# zx80_SD_12_smd_build006_2_STM32.net
KiCad netlist of a schematic drawn in EAGLE
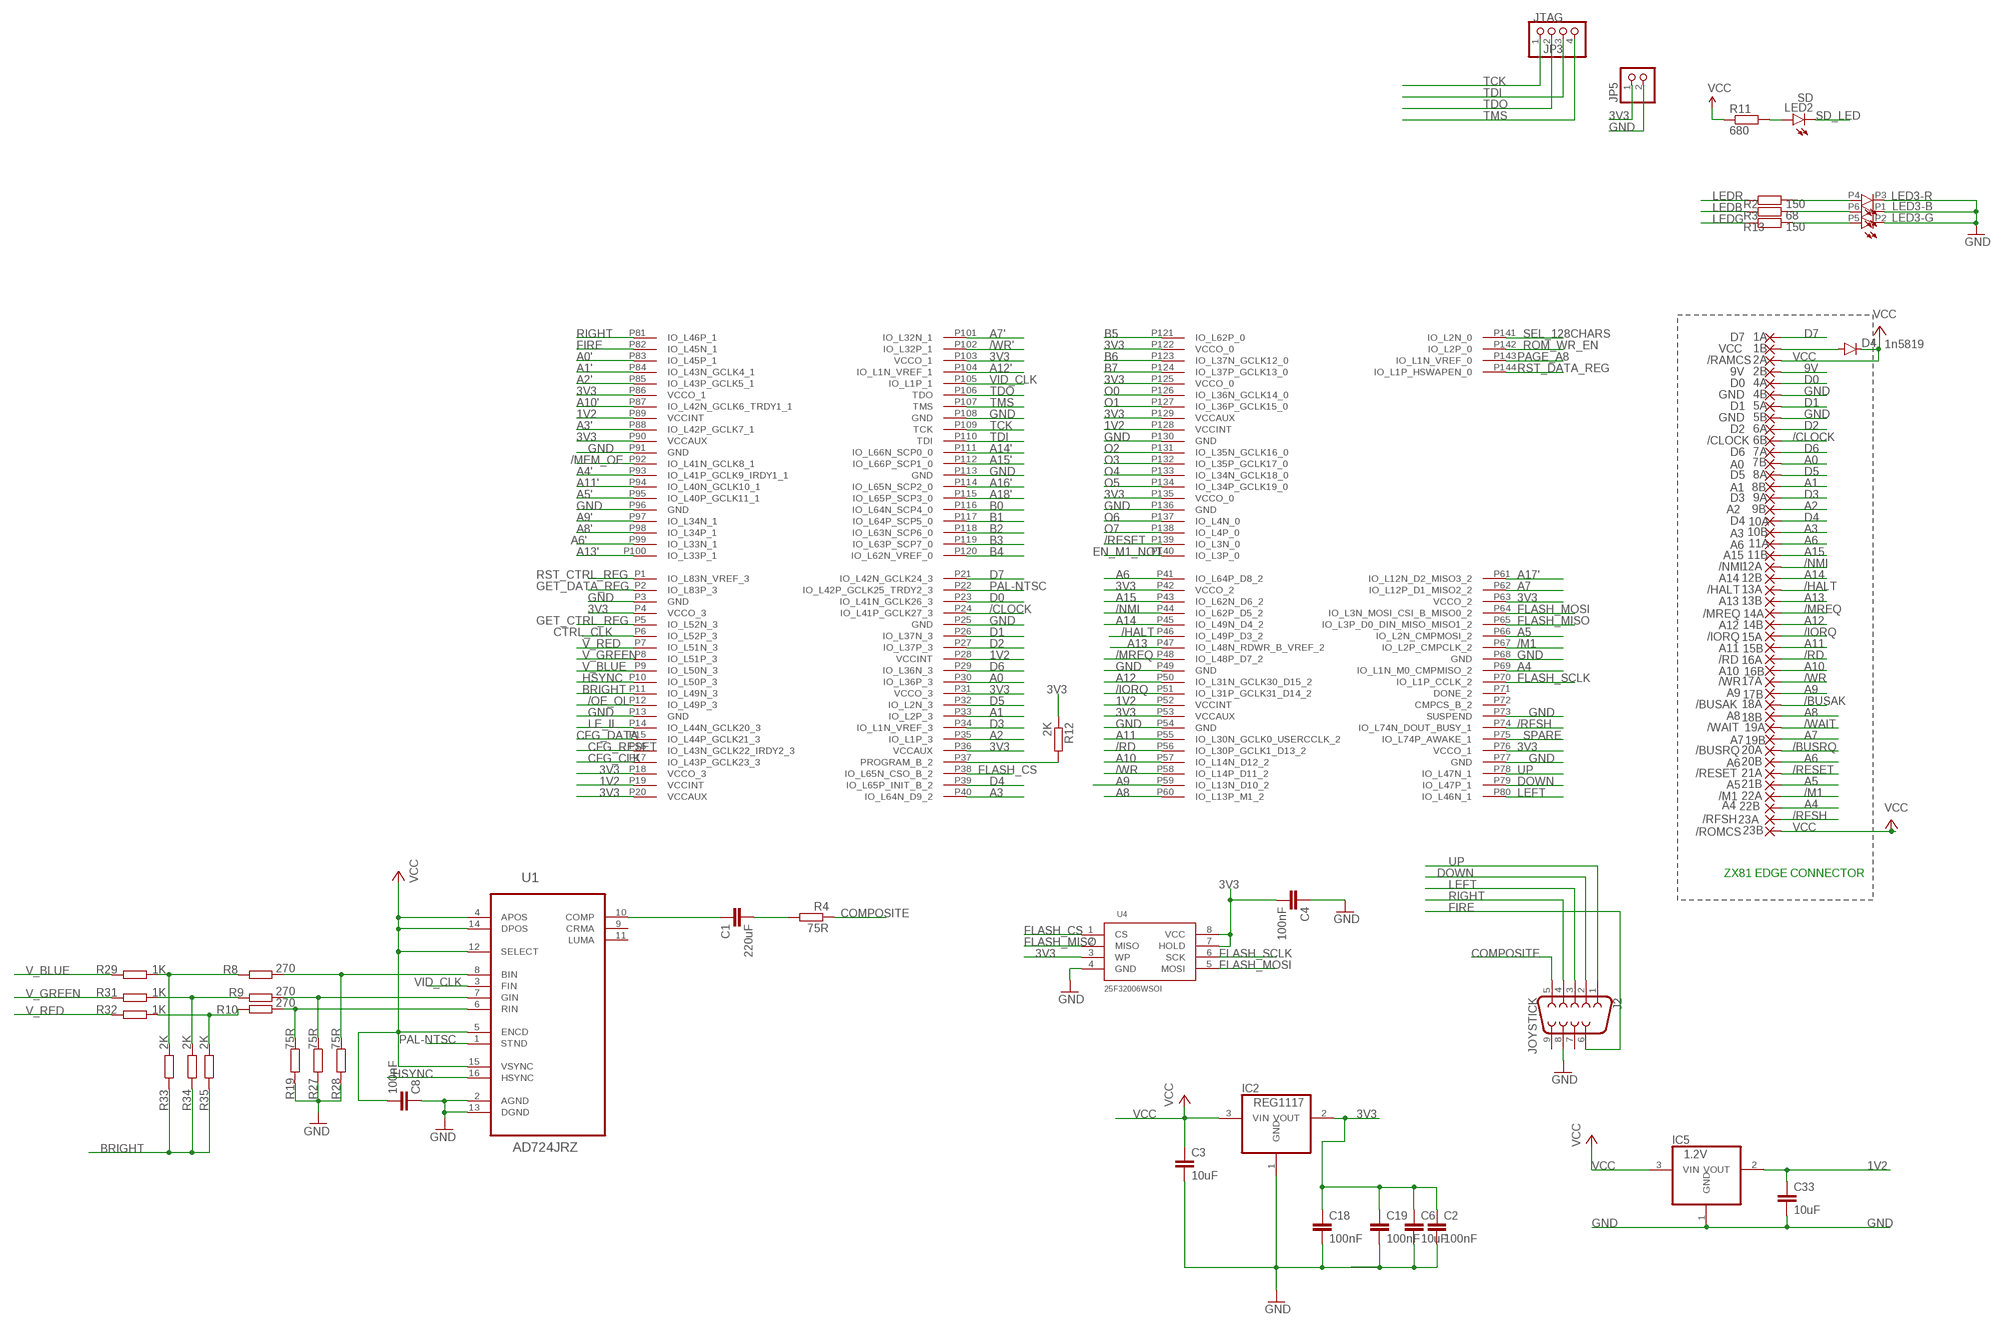
[diagram p0: schematic, sheet 1, part 1 of 2]
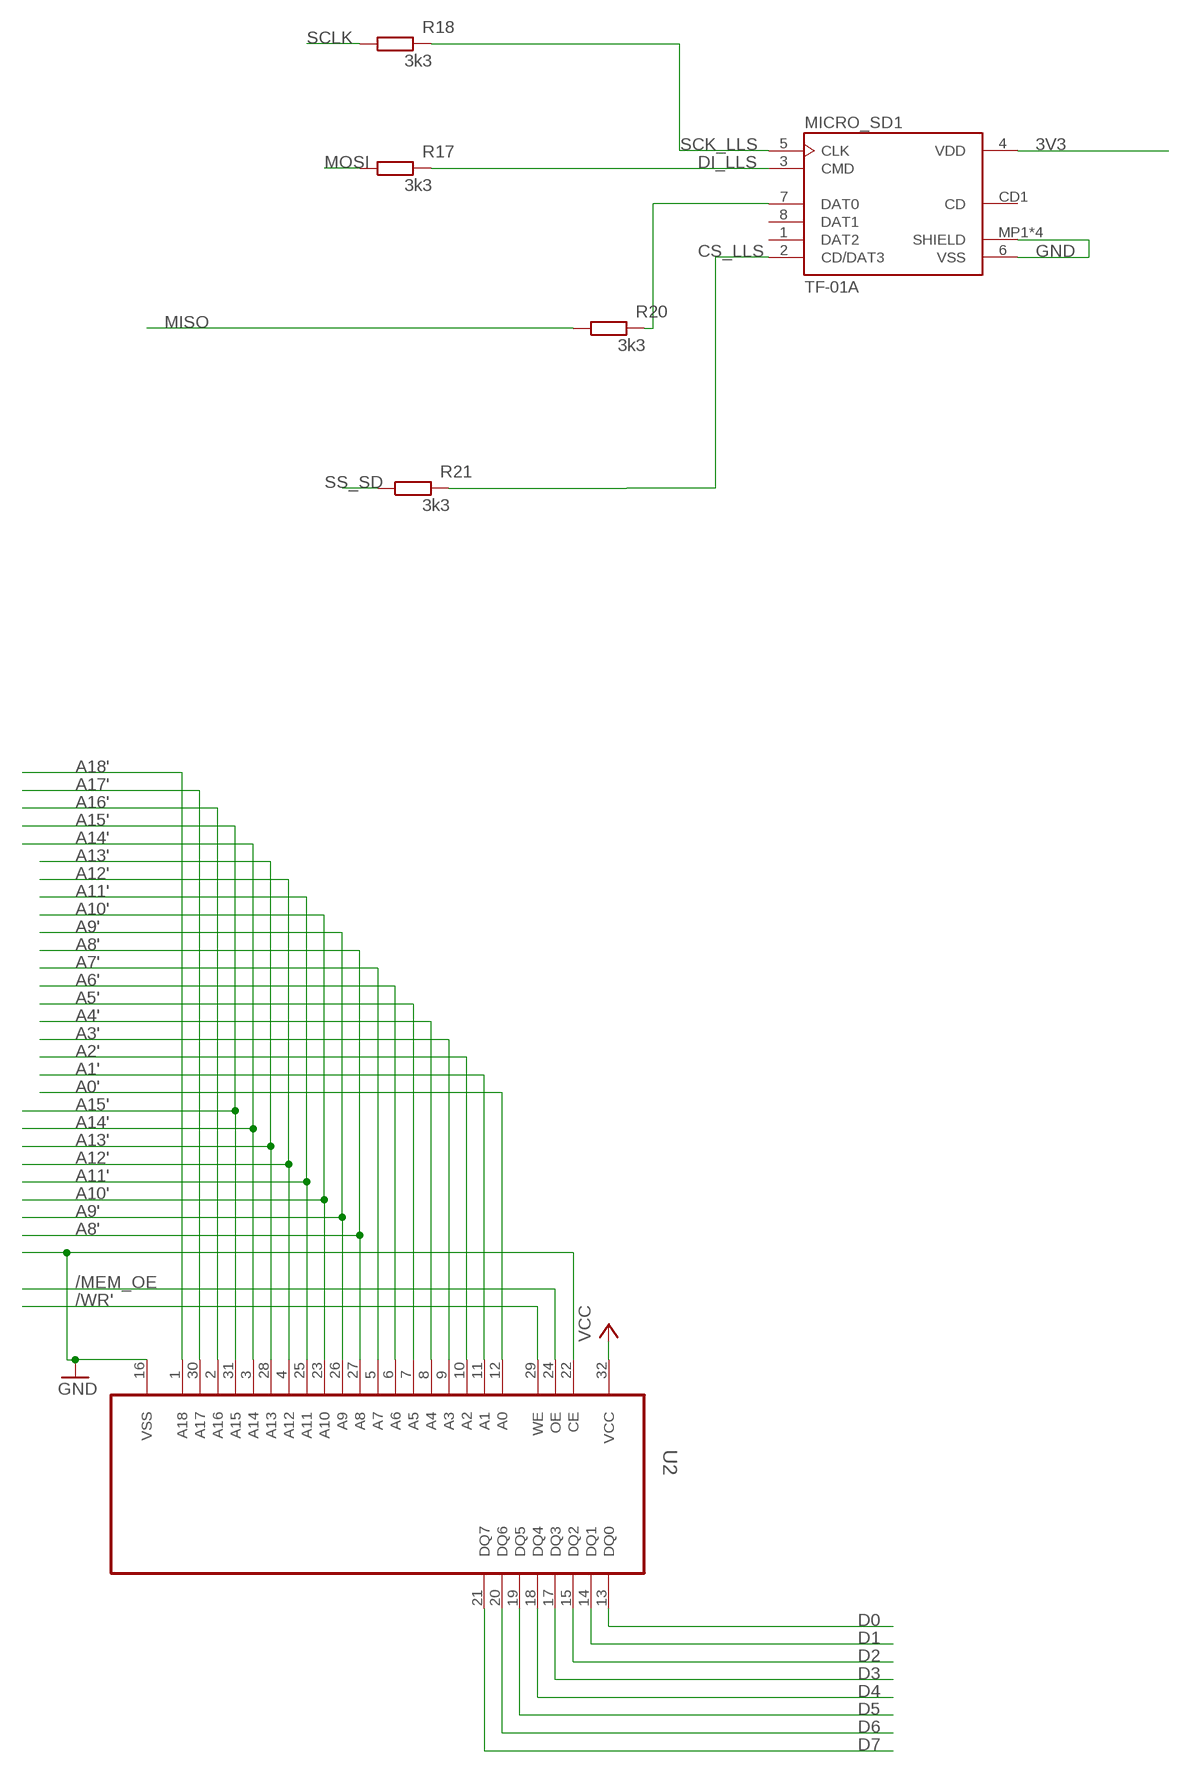
[diagram p1: schematic, sheet 1, part 2 of 2]
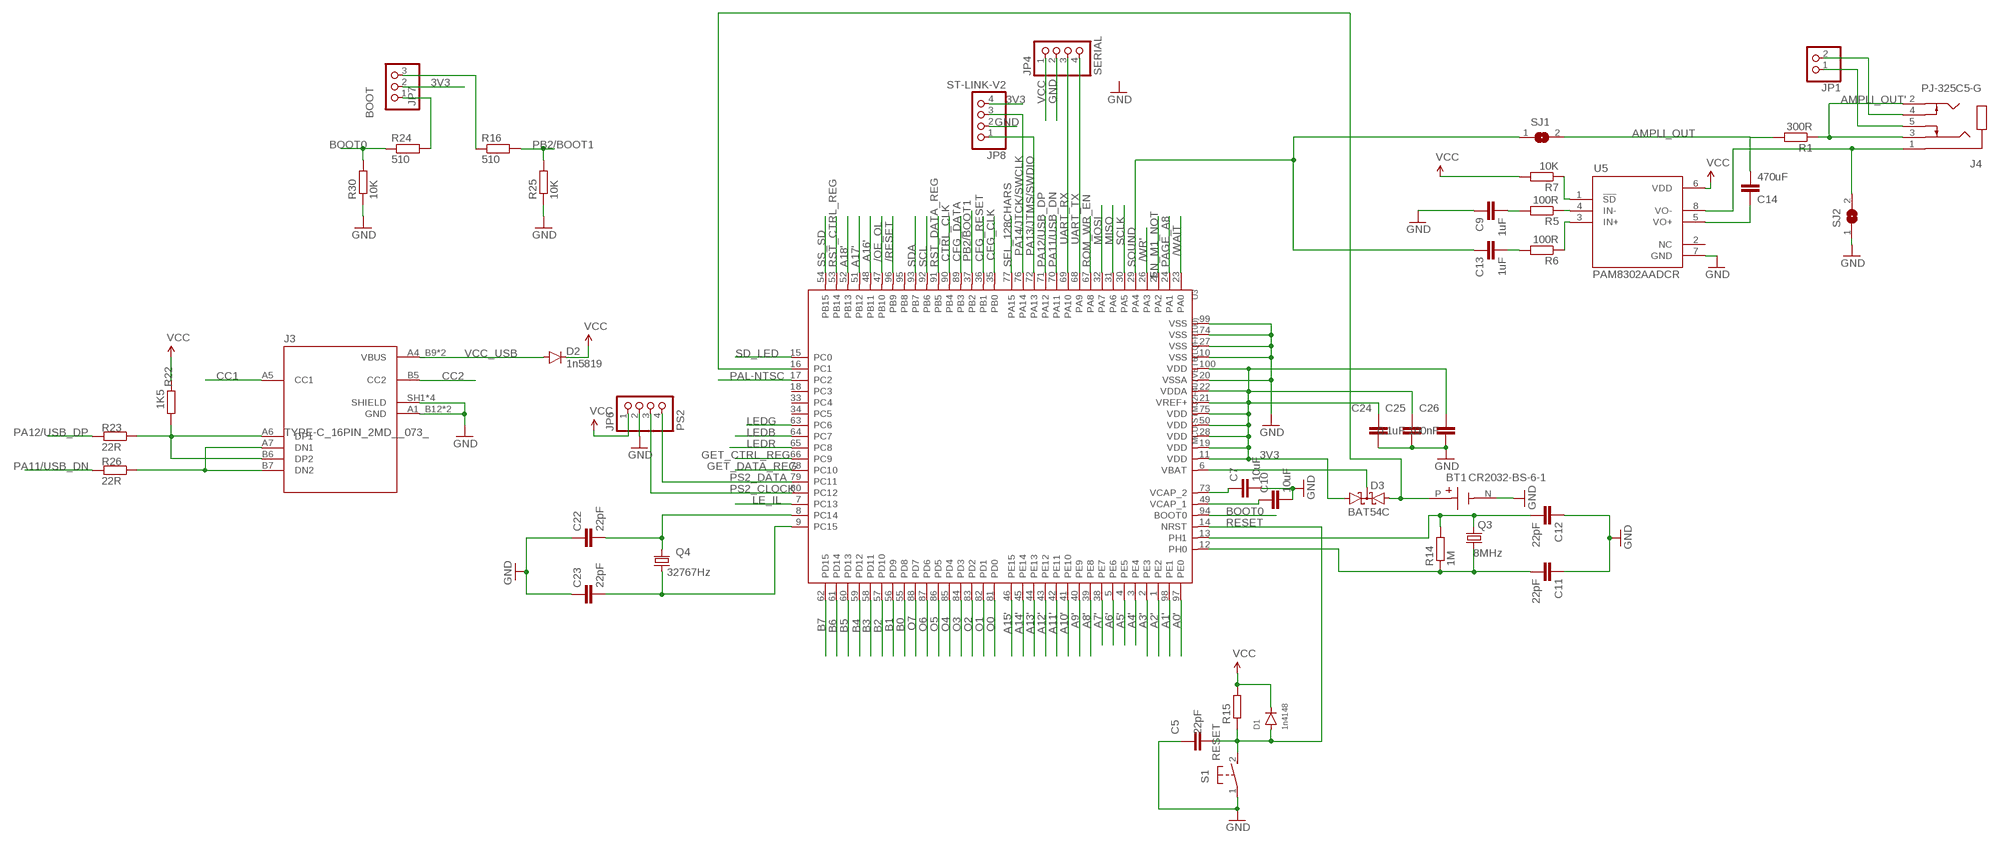
[diagram p2: schematic, sheet 2]

(export (version "E")
  (design (tool "Eeschema 10.0.6"))
  (components
    (comp (ref "BT1")
      (value "CR2032-BS-6-1")
      (footprint "eagle-import:BAT_CR2032-BS-6-1")
      (fields (field (name "MF") "Shenzhen Q&J Electronics Co. Ltd"))
      (libsource (lib "eagle-import") (part "CR2032-BS-6-1"))
    )
    (comp (ref "C5")
      (value "22pF")
      (footprint "eagle-import:C0603")
      (libsource (lib "eagle-import") (part "C-EUC0603"))
    )
    (comp (ref "C7")
      (value "10uF")
      (footprint "eagle-import:C1206")
      (libsource (lib "eagle-import") (part "C-EUC1206"))
    )
    (comp (ref "C9")
      (value "1uF")
      (footprint "eagle-import:C0603")
      (libsource (lib "eagle-import") (part "C-EUC0603"))
    )
    (comp (ref "C10")
      (value "10uF")
      (footprint "eagle-import:C1206")
      (libsource (lib "eagle-import") (part "C-EUC1206"))
    )
    (comp (ref "C11")
      (value "22pF")
      (footprint "eagle-import:C0603")
      (libsource (lib "eagle-import") (part "C-EUC0603"))
    )
    (comp (ref "C12")
      (value "22pF")
      (footprint "eagle-import:C0603")
      (libsource (lib "eagle-import") (part "C-EUC0603"))
    )
    (comp (ref "C13")
      (value "1uF")
      (footprint "eagle-import:C0603")
      (libsource (lib "eagle-import") (part "C-EUC0603"))
    )
    (comp (ref "C14")
      (value "470uF")
      (footprint "eagle-import:C0603")
      (libsource (lib "eagle-import") (part "C-EUC0603"))
    )
    (comp (ref "C22")
      (value "22pF")
      (footprint "eagle-import:C0603")
      (libsource (lib "eagle-import") (part "C-EUC0603"))
    )
    (comp (ref "C23")
      (value "22pF")
      (footprint "eagle-import:C0603")
      (libsource (lib "eagle-import") (part "C-EUC0603"))
    )
    (comp (ref "C24")
      (value "0.1uF")
      (footprint "eagle-import:C0603")
      (libsource (lib "eagle-import") (part "C-EUC0603"))
    )
    (comp (ref "C25")
      (value "0.1uF")
      (footprint "eagle-import:C0603")
      (libsource (lib "eagle-import") (part "C-EUC0603"))
    )
    (comp (ref "C26")
      (value "100nF")
      (footprint "eagle-import:C0603")
      (libsource (lib "eagle-import") (part "C-EUC0603"))
    )
    (comp (ref "D1")
      (value "1n4148")
      (footprint "eagle-import:SOD123")
      (libsource (lib "eagle-import") (part "DIODE-SOD123"))
    )
    (comp (ref "D2")
      (value "1n5819")
      (footprint "eagle-import:SOD323-W")
      (libsource (lib "eagle-import") (part "DIODE-SOD323-W"))
    )
    (comp (ref "D3")
      (value "BAT54C")
      (footprint "eagle-import:SOT23")
      (libsource (lib "eagle-import") (part "BAT54C"))
    )
    (comp (ref "J3")
      (value "TYPE-C_16PIN_2MD__073_")
      (footprint "eagle-import:SHOUHAN_TYPE-C_16PIN_2MD__073_")
      (fields (field (name "MF") "Shouhan") (field (name "MP") "TYPE-C 16PIN 2MD (073)"))
      (libsource (lib "eagle-import") (part "TYPE-C_16PIN_2MD__073_"))
    )
    (comp (ref "J4")
      (value "PJ-325C5-G")
      (footprint "eagle-import:XKB_PJ-325C5-G")
      (fields (field (name "MF") "XKB Connection"))
      (libsource (lib "eagle-import") (part "PJ-325C5-G"))
    )
    (comp (ref "JP1")
      (value "PINHD-1X2")
      (footprint "eagle-import:1X02")
      (libsource (lib "eagle-import") (part "PINHD-1X2"))
    )
    (comp (ref "JP4")
      (value "SERIAL")
      (footprint "eagle-import:1X04")
      (libsource (lib "eagle-import") (part "PINHD-1X4"))
    )
    (comp (ref "JP6")
      (value "PS2")
      (footprint "eagle-import:1X04")
      (libsource (lib "eagle-import") (part "PINHD-1X4"))
    )
    (comp (ref "JP7")
      (value "BOOT")
      (footprint "eagle-import:1X03")
      (libsource (lib "eagle-import") (part "PINHD-1X3"))
    )
    (comp (ref "JP8")
      (value "ST-LINK-V2")
      (footprint "eagle-import:1X04")
      (libsource (lib "eagle-import") (part "PINHD-1X4"))
    )
    (comp (ref "Q3")
      (value "8MHz")
      (footprint "eagle-import:3.2X2.5_KX-7")
      (libsource (lib "eagle-import") (part "KX-7"))
    )
    (comp (ref "Q4")
      (value "32767Hz")
      (footprint "eagle-import:3.2X1.5")
      (libsource (lib "eagle-import") (part "KX-327-NHT"))
    )
    (comp (ref "R1")
      (value "300R")
      (footprint "eagle-import:R0603")
      (libsource (lib "eagle-import") (part "R-EU_R0603"))
    )
    (comp (ref "R5")
      (value "100R")
      (footprint "eagle-import:R0603")
      (libsource (lib "eagle-import") (part "R-EU_R0603"))
    )
    (comp (ref "R6")
      (value "100R")
      (footprint "eagle-import:R0603")
      (libsource (lib "eagle-import") (part "R-EU_R0603"))
    )
    (comp (ref "R7")
      (value "10K")
      (footprint "eagle-import:R0603")
      (libsource (lib "eagle-import") (part "R-EU_R0603"))
    )
    (comp (ref "R14")
      (value "1M")
      (footprint "eagle-import:R0603")
      (libsource (lib "eagle-import") (part "R-EU_R0603"))
    )
    (comp (ref "R15")
      (value "3K3")
      (footprint "eagle-import:R0603")
      (libsource (lib "eagle-import") (part "R-EU_R0603"))
    )
    (comp (ref "R16")
      (value "510")
      (footprint "eagle-import:R0603")
      (libsource (lib "eagle-import") (part "R-EU_R0603"))
    )
    (comp (ref "R22")
      (value "1K5")
      (footprint "eagle-import:R0603")
      (libsource (lib "eagle-import") (part "R-EU_R0603"))
    )
    (comp (ref "R23")
      (value "22R")
      (footprint "eagle-import:R0603")
      (libsource (lib "eagle-import") (part "R-EU_R0603"))
    )
    (comp (ref "R24")
      (value "510")
      (footprint "eagle-import:R0603")
      (libsource (lib "eagle-import") (part "R-EU_R0603"))
    )
    (comp (ref "R25")
      (value "10K")
      (footprint "eagle-import:R0603")
      (libsource (lib "eagle-import") (part "R-EU_R0603"))
    )
    (comp (ref "R26")
      (value "22R")
      (footprint "eagle-import:R0603")
      (libsource (lib "eagle-import") (part "R-EU_R0603"))
    )
    (comp (ref "R30")
      (value "10K")
      (footprint "eagle-import:R0603")
      (libsource (lib "eagle-import") (part "R-EU_R0603"))
    )
    (comp (ref "S1")
      (value "RESET")
      (footprint "eagle-import:B3F-31XX")
      (fields (field (name "MPN") "B3F-3100"))
      (libsource (lib "eagle-import") (part "31-XX"))
    )
    (comp (ref "SJ1") (value "SJ") (footprint "eagle-import:SJ") (libsource (lib "eagle-import") (part "SJ")))
    (comp (ref "SJ2") (value "SJ") (footprint "eagle-import:SJ") (libsource (lib "eagle-import") (part "SJ")))
    (comp (ref "U3")
      (value "MCU-STM32F407VET6(LQFP100)")
      (footprint "eagle-import:LQFP100-0.5-13.8X13.8MM")
      (fields (field (name "MF") "STMicroelectronics") (field (name "MP") "STM32F407VET6"))
      (libsource (lib "eagle-import") (part "MCU-STM32F407VET6(LQFP100)"))
    )
    (comp (ref "U5")
      (value "PAM8302AADCR")
      (footprint "eagle-import:SOIC127P600X170-8N")
      (fields (field (name "MF") "Diodes Inc."))
      (libsource (lib "eagle-import") (part "PAM8302AADCR"))
    )
    (comp (ref "1A")
      (value "D7")
      (footprint "eagle-import:EDGEPIN")
      (libsource (lib "eagle-import") (part "SMD2EDGEPIN"))
    )
    (comp (ref "1B")
      (value "VCC")
      (footprint "eagle-import:EDGEPIN")
      (libsource (lib "eagle-import") (part "SMD2EDGEPIN"))
    )
    (comp (ref "2A")
      (value "/RAMCS")
      (footprint "eagle-import:EDGEPIN")
      (libsource (lib "eagle-import") (part "SMD2EDGEPIN"))
    )
    (comp (ref "2B")
      (value "9V")
      (footprint "eagle-import:EDGEPIN")
      (libsource (lib "eagle-import") (part "SMD2EDGEPIN"))
    )
    (comp (ref "4A")
      (value "D0")
      (footprint "eagle-import:EDGEPIN")
      (libsource (lib "eagle-import") (part "SMD2EDGEPIN"))
    )
    (comp (ref "4B")
      (value "GND")
      (footprint "eagle-import:EDGEPIN")
      (libsource (lib "eagle-import") (part "SMD2EDGEPIN"))
    )
    (comp (ref "5A")
      (value "D1")
      (footprint "eagle-import:EDGEPIN")
      (libsource (lib "eagle-import") (part "SMD2EDGEPIN"))
    )
    (comp (ref "5B")
      (value "GND")
      (footprint "eagle-import:EDGEPIN")
      (libsource (lib "eagle-import") (part "SMD2EDGEPIN"))
    )
    (comp (ref "6A")
      (value "D2")
      (footprint "eagle-import:EDGEPIN")
      (libsource (lib "eagle-import") (part "SMD2EDGEPIN"))
    )
    (comp (ref "6B")
      (value "/CLOCK")
      (footprint "eagle-import:EDGEPIN")
      (libsource (lib "eagle-import") (part "SMD2EDGEPIN"))
    )
    (comp (ref "7A")
      (value "D6")
      (footprint "eagle-import:EDGEPIN")
      (libsource (lib "eagle-import") (part "SMD2EDGEPIN"))
    )
    (comp (ref "7B")
      (value "A0")
      (footprint "eagle-import:EDGEPIN")
      (libsource (lib "eagle-import") (part "SMD2EDGEPIN"))
    )
    (comp (ref "8A")
      (value "D5")
      (footprint "eagle-import:EDGEPIN")
      (libsource (lib "eagle-import") (part "SMD2EDGEPIN"))
    )
    (comp (ref "8B")
      (value "A1")
      (footprint "eagle-import:EDGEPIN")
      (libsource (lib "eagle-import") (part "SMD2EDGEPIN"))
    )
    (comp (ref "9A")
      (value "D3")
      (footprint "eagle-import:EDGEPIN")
      (libsource (lib "eagle-import") (part "SMD2EDGEPIN"))
    )
    (comp (ref "9B")
      (value "A2")
      (footprint "eagle-import:EDGEPIN")
      (libsource (lib "eagle-import") (part "SMD2EDGEPIN"))
    )
    (comp (ref "10A")
      (value "D4")
      (footprint "eagle-import:EDGEPIN")
      (libsource (lib "eagle-import") (part "SMD2EDGEPIN"))
    )
    (comp (ref "10B")
      (value "A3")
      (footprint "eagle-import:EDGEPIN")
      (libsource (lib "eagle-import") (part "SMD2EDGEPIN"))
    )
    (comp (ref "11A")
      (value "A6")
      (footprint "eagle-import:EDGEPIN")
      (libsource (lib "eagle-import") (part "SMD2EDGEPIN"))
    )
    (comp (ref "11B")
      (value "A15")
      (footprint "eagle-import:EDGEPIN")
      (libsource (lib "eagle-import") (part "SMD2EDGEPIN"))
    )
    (comp (ref "12A")
      (value "/NMI")
      (footprint "eagle-import:EDGEPIN")
      (libsource (lib "eagle-import") (part "SMD2EDGEPIN"))
    )
    (comp (ref "12B")
      (value "A14")
      (footprint "eagle-import:EDGEPIN")
      (libsource (lib "eagle-import") (part "SMD2EDGEPIN"))
    )
    (comp (ref "13A")
      (value "/HALT")
      (footprint "eagle-import:EDGEPIN")
      (libsource (lib "eagle-import") (part "SMD2EDGEPIN"))
    )
    (comp (ref "13B")
      (value "A13")
      (footprint "eagle-import:EDGEPIN")
      (libsource (lib "eagle-import") (part "SMD2EDGEPIN"))
    )
    (comp (ref "14A")
      (value "/MREQ")
      (footprint "eagle-import:EDGEPIN")
      (libsource (lib "eagle-import") (part "SMD2EDGEPIN"))
    )
    (comp (ref "14B")
      (value "A12")
      (footprint "eagle-import:EDGEPIN")
      (libsource (lib "eagle-import") (part "SMD2EDGEPIN"))
    )
    (comp (ref "15A")
      (value "/IORQ")
      (footprint "eagle-import:EDGEPIN")
      (libsource (lib "eagle-import") (part "SMD2EDGEPIN"))
    )
    (comp (ref "15B")
      (value "A11")
      (footprint "eagle-import:EDGEPIN")
      (libsource (lib "eagle-import") (part "SMD2EDGEPIN"))
    )
    (comp (ref "16A")
      (value "/RD")
      (footprint "eagle-import:EDGEPIN")
      (libsource (lib "eagle-import") (part "SMD2EDGEPIN"))
    )
    (comp (ref "16B")
      (value "A10")
      (footprint "eagle-import:EDGEPIN")
      (libsource (lib "eagle-import") (part "SMD2EDGEPIN"))
    )
    (comp (ref "17A")
      (value "/WR")
      (footprint "eagle-import:EDGEPIN")
      (libsource (lib "eagle-import") (part "SMD2EDGEPIN"))
    )
    (comp (ref "17B")
      (value "A9")
      (footprint "eagle-import:EDGEPIN")
      (libsource (lib "eagle-import") (part "SMD2EDGEPIN"))
    )
    (comp (ref "18A")
      (value "/BUSAK")
      (footprint "eagle-import:EDGEPIN")
      (libsource (lib "eagle-import") (part "SMD2EDGEPIN"))
    )
    (comp (ref "18B")
      (value "A8")
      (footprint "eagle-import:EDGEPIN")
      (libsource (lib "eagle-import") (part "SMD2EDGEPIN"))
    )
    (comp (ref "19A")
      (value "/WAIT")
      (footprint "eagle-import:EDGEPIN")
      (libsource (lib "eagle-import") (part "SMD2EDGEPIN"))
    )
    (comp (ref "19B")
      (value "A7")
      (footprint "eagle-import:EDGEPIN")
      (libsource (lib "eagle-import") (part "SMD2EDGEPIN"))
    )
    (comp (ref "20A")
      (value "/BUSRQ")
      (footprint "eagle-import:EDGEPIN")
      (libsource (lib "eagle-import") (part "SMD2EDGEPIN"))
    )
    (comp (ref "20B")
      (value "A6")
      (footprint "eagle-import:EDGEPIN")
      (libsource (lib "eagle-import") (part "SMD2EDGEPIN"))
    )
    (comp (ref "21A")
      (value "/RESET")
      (footprint "eagle-import:EDGEPIN")
      (libsource (lib "eagle-import") (part "SMD2EDGEPIN"))
    )
    (comp (ref "21B")
      (value "A5")
      (footprint "eagle-import:EDGEPIN")
      (libsource (lib "eagle-import") (part "SMD2EDGEPIN"))
    )
    (comp (ref "22A")
      (value "/M1")
      (footprint "eagle-import:EDGEPIN")
      (libsource (lib "eagle-import") (part "SMD2EDGEPIN"))
    )
    (comp (ref "22B")
      (value "A4")
      (footprint "eagle-import:EDGEPIN")
      (libsource (lib "eagle-import") (part "SMD2EDGEPIN"))
    )
    (comp (ref "23A")
      (value "/RFSH")
      (footprint "eagle-import:EDGEPIN")
      (libsource (lib "eagle-import") (part "SMD2EDGEPIN"))
    )
    (comp (ref "23B")
      (value "/ROMCS")
      (footprint "eagle-import:EDGEPIN")
      (libsource (lib "eagle-import") (part "SMD2EDGEPIN"))
    )
    (comp (ref "C1")
      (value "220uF")
      (footprint "eagle-import:C0603K")
      (libsource (lib "eagle-import") (part "C-EUC0603K"))
    )
    (comp (ref "C2")
      (value "100nF")
      (footprint "eagle-import:C0603")
      (libsource (lib "eagle-import") (part "C-EUC0603"))
    )
    (comp (ref "C3")
      (value "10uF")
      (footprint "eagle-import:C0603")
      (libsource (lib "eagle-import") (part "C-EUC0603"))
    )
    (comp (ref "C4")
      (value "100nF")
      (footprint "eagle-import:C0603")
      (libsource (lib "eagle-import") (part "C-EUC0603"))
    )
    (comp (ref "C6")
      (value "10uF")
      (footprint "eagle-import:C0603")
      (libsource (lib "eagle-import") (part "C-EUC0603"))
    )
    (comp (ref "C8")
      (value "100nF")
      (footprint "eagle-import:C0603K")
      (libsource (lib "eagle-import") (part "C-EUC0603K"))
    )
    (comp (ref "C18")
      (value "100nF")
      (footprint "eagle-import:C0603")
      (libsource (lib "eagle-import") (part "C-EUC0603"))
    )
    (comp (ref "C19")
      (value "100nF")
      (footprint "eagle-import:C0603")
      (libsource (lib "eagle-import") (part "C-EUC0603"))
    )
    (comp (ref "C33")
      (value "10uF")
      (footprint "eagle-import:C0603")
      (libsource (lib "eagle-import") (part "C-EUC0603"))
    )
    (comp (ref "D4")
      (value "1n5819")
      (footprint "eagle-import:SOD323-W")
      (libsource (lib "eagle-import") (part "DIODE-SOD323-W"))
    )
    (comp (ref "IC2")
      (value "REG1117")
      (footprint "eagle-import:SOT223")
      (libsource (lib "eagle-import") (part "REG1117"))
    )
    (comp (ref "IC5")
      (value "1.2V")
      (footprint "eagle-import:SOT223")
      (fields (field (name "MPN") "REG1117"))
      (libsource (lib "eagle-import") (part "REG1117"))
    )
    (comp (ref "J2")
      (value "JOYSTICK")
      (footprint "eagle-import:DB9_MALE")
      (libsource (lib "eagle-import") (part "DB9MALE"))
    )
    (comp (ref "JP3")
      (value "JTAG")
      (footprint "eagle-import:1X04")
      (libsource (lib "eagle-import") (part "PINHD-1X4"))
    )
    (comp (ref "JP5")
      (value "PINHD-1X2")
      (footprint "eagle-import:1X02")
      (libsource (lib "eagle-import") (part "PINHD-1X2"))
    )
    (comp (ref "LED2")
      (value "SD")
      (footprint "eagle-import:CHIPLED_0805")
      (libsource (lib "eagle-import") (part "LEDCHIPLED_0805"))
    )
    (comp (ref "LED3")
      (value "STATUS")
      (footprint "eagle-import:3535-PLCC6")
      (libsource (lib "eagle-import") (part "3535RGB3535RGB"))
    )
    (comp (ref "MICRO_SD1")
      (value "TF-01A")
      (footprint "eagle-import:TF-01A")
      (fields (field (name "MF") "HRO Electronics Co., Ltd."))
      (libsource (lib "eagle-import") (part "TF-01A"))
    )
    (comp (ref "R2")
      (value "150")
      (footprint "eagle-import:R0603")
      (libsource (lib "eagle-import") (part "R-EU_R0603"))
    )
    (comp (ref "R3")
      (value "68")
      (footprint "eagle-import:R0603")
      (libsource (lib "eagle-import") (part "R-EU_R0603"))
    )
    (comp (ref "R4")
      (value "75R")
      (footprint "eagle-import:R0603")
      (libsource (lib "eagle-import") (part "R-EU_R0603"))
    )
    (comp (ref "R8")
      (value "270")
      (footprint "eagle-import:R0402")
      (libsource (lib "eagle-import") (part "R-EU_R0402"))
    )
    (comp (ref "R9")
      (value "270")
      (footprint "eagle-import:R0402")
      (libsource (lib "eagle-import") (part "R-EU_R0402"))
    )
    (comp (ref "R10")
      (value "270")
      (footprint "eagle-import:R0402")
      (libsource (lib "eagle-import") (part "R-EU_R0402"))
    )
    (comp (ref "R11")
      (value "680")
      (footprint "eagle-import:R0603")
      (libsource (lib "eagle-import") (part "R-EU_R0603"))
    )
    (comp (ref "R12")
      (value "2K")
      (footprint "eagle-import:R0603")
      (libsource (lib "eagle-import") (part "R-EU_R0603"))
    )
    (comp (ref "R13")
      (value "150")
      (footprint "eagle-import:R0603")
      (libsource (lib "eagle-import") (part "R-EU_R0603"))
    )
    (comp (ref "R17")
      (value "3k3")
      (footprint "eagle-import:R0603")
      (libsource (lib "eagle-import") (part "R-EU_R0603"))
    )
    (comp (ref "R18")
      (value "3k3")
      (footprint "eagle-import:R0603")
      (libsource (lib "eagle-import") (part "R-EU_R0603"))
    )
    (comp (ref "R19")
      (value "75R")
      (footprint "eagle-import:R0402")
      (libsource (lib "eagle-import") (part "R-EU_R0402"))
    )
    (comp (ref "R20")
      (value "3k3")
      (footprint "eagle-import:R0603")
      (libsource (lib "eagle-import") (part "R-EU_R0603"))
    )
    (comp (ref "R21")
      (value "3k3")
      (footprint "eagle-import:R0603")
      (libsource (lib "eagle-import") (part "R-EU_R0603"))
    )
    (comp (ref "R27")
      (value "75R")
      (footprint "eagle-import:R0402")
      (libsource (lib "eagle-import") (part "R-EU_R0402"))
    )
    (comp (ref "R28")
      (value "75R")
      (footprint "eagle-import:R0402")
      (libsource (lib "eagle-import") (part "R-EU_R0402"))
    )
    (comp (ref "R29")
      (value "1K")
      (footprint "eagle-import:R0402")
      (libsource (lib "eagle-import") (part "R-EU_R0402"))
    )
    (comp (ref "R31")
      (value "1K")
      (footprint "eagle-import:R0402")
      (libsource (lib "eagle-import") (part "R-EU_R0402"))
    )
    (comp (ref "R32")
      (value "1K")
      (footprint "eagle-import:R0402")
      (libsource (lib "eagle-import") (part "R-EU_R0402"))
    )
    (comp (ref "R33")
      (value "2K")
      (footprint "eagle-import:R0402")
      (libsource (lib "eagle-import") (part "R-EU_R0402"))
    )
    (comp (ref "R34")
      (value "2K")
      (footprint "eagle-import:R0402")
      (libsource (lib "eagle-import") (part "R-EU_R0402"))
    )
    (comp (ref "R35")
      (value "2K")
      (footprint "eagle-import:R0402")
      (libsource (lib "eagle-import") (part "R-EU_R0402"))
    )
    (comp (ref "U$1")
      (value "XC6SLX9-2TQG144C")
      (footprint "eagle-import:TQ144")
      (fields (field (name "MF") "Xilinx Inc."))
      (libsource (lib "eagle-import") (part "XC6SLX9-2TQG144C"))
    )
    (comp (ref "U1")
      (value "AD724JRZ")
      (footprint "eagle-import:SOIC127P1032X265-16N")
      (fields (field (name "MF") "Analog Devices") (field (name "MP") "AD724JR"))
      (libsource (lib "eagle-import") (part "AD724JRZ"))
    )
    (comp (ref "U2")
      (value "AS6C4008")
      (footprint "eagle-import:SOP32-5")
      (libsource (lib "eagle-import") (part "AS6C4008-55SINSOP5"))
    )
    (comp (ref "U4")
      (value "25F32006WSOI")
      (footprint "eagle-import:SO08-EIAJ")
      (libsource (lib "eagle-import") (part "SPI_FLASH-X25XXSMD1"))
    )
  )
  (nets
    (net (code "1") (name "1V2") (class "Default")
      (node (ref "C33") (pin "1") (pinfunction "1_1") (pintype "passive"))
      (node (ref "IC5") (pin "2") (pinfunction "VOUT_2") (pintype "output"))
      (node (ref "U$1") (pin "P128") (pinfunction "VCCINT_P128") (pintype "bidirectional"))
      (node (ref "U$1") (pin "P19") (pinfunction "VCCINT_P19") (pintype "bidirectional"))
      (node (ref "U$1") (pin "P28") (pinfunction "VCCINT_P28") (pintype "bidirectional"))
      (node (ref "U$1") (pin "P52") (pinfunction "VCCINT_P52") (pintype "bidirectional"))
      (node (ref "U$1") (pin "P89") (pinfunction "VCCINT_P89") (pintype "bidirectional"))
    )
    (net (code "2") (name "3V3") (class "Default")
      (node (ref "C18") (pin "1") (pinfunction "1_1") (pintype "passive"))
      (node (ref "C19") (pin "1") (pinfunction "1_1") (pintype "passive"))
      (node (ref "C2") (pin "1") (pinfunction "1_1") (pintype "passive"))
      (node (ref "C24") (pin "1") (pinfunction "1_1") (pintype "passive"))
      (node (ref "C25") (pin "1") (pinfunction "1_1") (pintype "passive"))
      (node (ref "C26") (pin "1") (pinfunction "1_1") (pintype "passive"))
      (node (ref "C4") (pin "2") (pinfunction "2_2") (pintype "passive"))
      (node (ref "C6") (pin "1") (pinfunction "1_1") (pintype "passive"))
      (node (ref "D3") (pin "1") (pinfunction "A1_1") (pintype "passive"))
      (node (ref "IC2") (pin "2") (pinfunction "VOUT_2") (pintype "output"))
      (node (ref "JP5") (pin "1") (pinfunction "1_1") (pintype "passive"))
      (node (ref "JP7") (pin "2") (pinfunction "2_2") (pintype "passive"))
      (node (ref "JP8") (pin "4") (pinfunction "4_4") (pintype "passive"))
      (node (ref "MICRO_SD1") (pin "4") (pinfunction "VDD_4") (pintype "power_in"))
      (node (ref "R12") (pin "1") (pinfunction "1_1") (pintype "passive"))
      (node (ref "U$1") (pin "P103") (pinfunction "VCCO_1_P103") (pintype "bidirectional"))
      (node (ref "U$1") (pin "P122") (pinfunction "VCCO_0_P122") (pintype "bidirectional"))
      (node (ref "U$1") (pin "P125") (pinfunction "VCCO_0_P125") (pintype "bidirectional"))
      (node (ref "U$1") (pin "P129") (pinfunction "VCCAUX_P129") (pintype "bidirectional"))
      (node (ref "U$1") (pin "P135") (pinfunction "VCCO_0_P135") (pintype "bidirectional"))
      (node (ref "U$1") (pin "P18") (pinfunction "VCCO_3_P18") (pintype "bidirectional"))
      (node (ref "U$1") (pin "P20") (pinfunction "VCCAUX_P20") (pintype "bidirectional"))
      (node (ref "U$1") (pin "P31") (pinfunction "VCCO_3_P31") (pintype "bidirectional"))
      (node (ref "U$1") (pin "P36") (pinfunction "VCCAUX_P36") (pintype "bidirectional"))
      (node (ref "U$1") (pin "P4") (pinfunction "VCCO_3_P4") (pintype "bidirectional"))
      (node (ref "U$1") (pin "P42") (pinfunction "VCCO_2_P42") (pintype "bidirectional"))
      (node (ref "U$1") (pin "P53") (pinfunction "VCCAUX_P53") (pintype "bidirectional"))
      (node (ref "U$1") (pin "P63") (pinfunction "VCCO_2_P63") (pintype "bidirectional"))
      (node (ref "U$1") (pin "P76") (pinfunction "VCCO_1_P76") (pintype "bidirectional"))
      (node (ref "U$1") (pin "P86") (pinfunction "VCCO_1_P86") (pintype "bidirectional"))
      (node (ref "U$1") (pin "P90") (pinfunction "VCCAUX_P90") (pintype "bidirectional"))
      (node (ref "U3") (pin "100") (pinfunction "VDD_100") (pintype "bidirectional"))
      (node (ref "U3") (pin "11") (pinfunction "VDD_11") (pintype "bidirectional"))
      (node (ref "U3") (pin "19") (pinfunction "VDD_19") (pintype "bidirectional"))
      (node (ref "U3") (pin "21") (pinfunction "VREF+_21") (pintype "bidirectional"))
      (node (ref "U3") (pin "22") (pinfunction "VDDA_22") (pintype "bidirectional"))
      (node (ref "U3") (pin "28") (pinfunction "VDD_28") (pintype "bidirectional"))
      (node (ref "U3") (pin "50") (pinfunction "VDD_50") (pintype "bidirectional"))
      (node (ref "U3") (pin "75") (pinfunction "VDD_75") (pintype "bidirectional"))
      (node (ref "U4") (pin "3") (pinfunction "WP_3") (pintype "bidirectional"))
      (node (ref "U4") (pin "7") (pinfunction "HOLD_7") (pintype "bidirectional"))
      (node (ref "U4") (pin "8") (pinfunction "VCC_8") (pintype "power_in"))
    )
    (net (code "3") (name "9V") (class "Default")
      (node (ref "2B") (pin "1") (pinfunction "P_1") (pintype "passive"))
    )
    (net (code "4") (name "A0") (class "Default")
      (node (ref "7B") (pin "1") (pinfunction "P_1") (pintype "passive"))
      (node (ref "U$1") (pin "P30") (pinfunction "IO_L36P_3_P30") (pintype "bidirectional"))
    )
    (net (code "5") (name "A0'") (class "Default")
      (node (ref "U$1") (pin "P83") (pinfunction "IO_L45P_1_P83") (pintype "bidirectional"))
      (node (ref "U2") (pin "12") (pinfunction "A0_12") (pintype "input"))
      (node (ref "U3") (pin "97") (pinfunction "PE0_97") (pintype "bidirectional"))
    )
    (net (code "6") (name "A1") (class "Default")
      (node (ref "8B") (pin "1") (pinfunction "P_1") (pintype "passive"))
      (node (ref "U$1") (pin "P33") (pinfunction "IO_L2P_3_P33") (pintype "bidirectional"))
    )
    (net (code "7") (name "A1'") (class "Default")
      (node (ref "U$1") (pin "P84") (pinfunction "IO_L43N_GCLK4_1_P84") (pintype "bidirectional"))
      (node (ref "U2") (pin "11") (pinfunction "A1_11") (pintype "input"))
      (node (ref "U3") (pin "98") (pinfunction "PE1_98") (pintype "bidirectional"))
    )
    (net (code "8") (name "A2") (class "Default")
      (node (ref "9B") (pin "1") (pinfunction "P_1") (pintype "passive"))
      (node (ref "U$1") (pin "P35") (pinfunction "IO_L1P_3_P35") (pintype "bidirectional"))
    )
    (net (code "9") (name "A2'") (class "Default")
      (node (ref "U$1") (pin "P85") (pinfunction "IO_L43P_GCLK5_1_P85") (pintype "bidirectional"))
      (node (ref "U2") (pin "10") (pinfunction "A2_10") (pintype "input"))
      (node (ref "U3") (pin "1") (pinfunction "PE2_1") (pintype "bidirectional"))
    )
    (net (code "10") (name "A3") (class "Default")
      (node (ref "10B") (pin "1") (pinfunction "P_1") (pintype "passive"))
      (node (ref "U$1") (pin "P40") (pinfunction "IO_L64N_D9_2_P40") (pintype "bidirectional"))
    )
    (net (code "11") (name "A3'") (class "Default")
      (node (ref "U$1") (pin "P88") (pinfunction "IO_L42P_GCLK7_1_P88") (pintype "bidirectional"))
      (node (ref "U2") (pin "9") (pinfunction "A3_9") (pintype "input"))
      (node (ref "U3") (pin "2") (pinfunction "PE3_2") (pintype "bidirectional"))
    )
    (net (code "12") (name "A4") (class "Default")
      (node (ref "22B") (pin "1") (pinfunction "P_1") (pintype "passive"))
      (node (ref "U$1") (pin "P69") (pinfunction "IO_L1N_M0_CMPMISO_2_P69") (pintype "bidirectional"))
    )
    (net (code "13") (name "A4'") (class "Default")
      (node (ref "U$1") (pin "P93") (pinfunction "IO_L41P_GCLK9_IRDY1_1_P93") (pintype "bidirectional"))
      (node (ref "U2") (pin "8") (pinfunction "A4_8") (pintype "input"))
      (node (ref "U3") (pin "3") (pinfunction "PE4_3") (pintype "bidirectional"))
    )
    (net (code "14") (name "A5") (class "Default")
      (node (ref "21B") (pin "1") (pinfunction "P_1") (pintype "passive"))
      (node (ref "U$1") (pin "P66") (pinfunction "IO_L2N_CMPMOSI_2_P66") (pintype "bidirectional"))
    )
    (net (code "15") (name "A5'") (class "Default")
      (node (ref "U$1") (pin "P95") (pinfunction "IO_L40P_GCLK11_1_P95") (pintype "bidirectional"))
      (node (ref "U2") (pin "7") (pinfunction "A5_7") (pintype "input"))
      (node (ref "U3") (pin "4") (pinfunction "PE5_4") (pintype "bidirectional"))
    )
    (net (code "16") (name "A6") (class "Default")
      (node (ref "11A") (pin "1") (pinfunction "P_1") (pintype "passive"))
      (node (ref "20B") (pin "1") (pinfunction "P_1") (pintype "passive"))
      (node (ref "U$1") (pin "P41") (pinfunction "IO_L64P_D8_2_P41") (pintype "bidirectional"))
    )
    (net (code "17") (name "A6'") (class "Default")
      (node (ref "U$1") (pin "P99") (pinfunction "IO_L33N_1_P99") (pintype "bidirectional"))
      (node (ref "U2") (pin "6") (pinfunction "A6_6") (pintype "input"))
      (node (ref "U3") (pin "5") (pinfunction "PE6_5") (pintype "bidirectional"))
    )
    (net (code "18") (name "A7") (class "Default")
      (node (ref "19B") (pin "1") (pinfunction "P_1") (pintype "passive"))
      (node (ref "U$1") (pin "P62") (pinfunction "IO_L12P_D1_MISO2_2_P62") (pintype "bidirectional"))
    )
    (net (code "19") (name "A7'") (class "Default")
      (node (ref "U$1") (pin "P101") (pinfunction "IO_L32N_1_P101") (pintype "bidirectional"))
      (node (ref "U2") (pin "5") (pinfunction "A7_5") (pintype "input"))
      (node (ref "U3") (pin "38") (pinfunction "PE7_38") (pintype "bidirectional"))
    )
    (net (code "20") (name "A8") (class "Default")
      (node (ref "18B") (pin "1") (pinfunction "P_1") (pintype "passive"))
      (node (ref "U$1") (pin "P60") (pinfunction "IO_L13P_M1_2_P60") (pintype "bidirectional"))
    )
    (net (code "21") (name "A8'") (class "Default")
      (node (ref "U$1") (pin "P98") (pinfunction "IO_L34P_1_P98") (pintype "bidirectional"))
      (node (ref "U2") (pin "27") (pinfunction "A8_27") (pintype "input"))
      (node (ref "U3") (pin "39") (pinfunction "PE8_39") (pintype "bidirectional"))
    )
    (net (code "22") (name "A9") (class "Default")
      (node (ref "17B") (pin "1") (pinfunction "P_1") (pintype "passive"))
      (node (ref "U$1") (pin "P59") (pinfunction "IO_L13N_D10_2_P59") (pintype "bidirectional"))
    )
    (net (code "23") (name "A9'") (class "Default")
      (node (ref "U$1") (pin "P97") (pinfunction "IO_L34N_1_P97") (pintype "bidirectional"))
      (node (ref "U2") (pin "26") (pinfunction "A9_26") (pintype "input"))
      (node (ref "U3") (pin "40") (pinfunction "PE9_40") (pintype "bidirectional"))
    )
    (net (code "24") (name "A10") (class "Default")
      (node (ref "16B") (pin "1") (pinfunction "P_1") (pintype "passive"))
      (node (ref "U$1") (pin "P57") (pinfunction "IO_L14N_D12_2_P57") (pintype "bidirectional"))
    )
    (net (code "25") (name "A10'") (class "Default")
      (node (ref "U$1") (pin "P87") (pinfunction "IO_L42N_GCLK6_TRDY1_1_P87") (pintype "bidirectional"))
      (node (ref "U2") (pin "23") (pinfunction "A10_23") (pintype "input"))
      (node (ref "U3") (pin "41") (pinfunction "PE10_41") (pintype "bidirectional"))
    )
    (net (code "26") (name "A11") (class "Default")
      (node (ref "15B") (pin "1") (pinfunction "P_1") (pintype "passive"))
      (node (ref "U$1") (pin "P55") (pinfunction "IO_L30N_GCLK0_USERCCLK_2_P55") (pintype "bidirectional"))
    )
    (net (code "27") (name "A11'") (class "Default")
      (node (ref "U$1") (pin "P94") (pinfunction "IO_L40N_GCLK10_1_P94") (pintype "bidirectional"))
      (node (ref "U2") (pin "25") (pinfunction "A11_25") (pintype "input"))
      (node (ref "U3") (pin "42") (pinfunction "PE11_42") (pintype "bidirectional"))
    )
    (net (code "28") (name "A12") (class "Default")
      (node (ref "14B") (pin "1") (pinfunction "P_1") (pintype "passive"))
      (node (ref "U$1") (pin "P50") (pinfunction "IO_L31N_GCLK30_D15_2_P50") (pintype "bidirectional"))
    )
    (net (code "29") (name "A12'") (class "Default")
      (node (ref "U$1") (pin "P104") (pinfunction "IO_L1N_VREF_1_P104") (pintype "bidirectional"))
      (node (ref "U2") (pin "4") (pinfunction "A12_4") (pintype "input"))
      (node (ref "U3") (pin "43") (pinfunction "PE12_43") (pintype "bidirectional"))
    )
    (net (code "30") (name "A13") (class "Default")
      (node (ref "13B") (pin "1") (pinfunction "P_1") (pintype "passive"))
      (node (ref "U$1") (pin "P47") (pinfunction "IO_L48N_RDWR_B_VREF_2_P47") (pintype "bidirectional"))
    )
    (net (code "31") (name "A13'") (class "Default")
      (node (ref "U$1") (pin "P100") (pinfunction "IO_L33P_1_P100") (pintype "bidirectional"))
      (node (ref "U2") (pin "28") (pinfunction "A13_28") (pintype "input"))
      (node (ref "U3") (pin "44") (pinfunction "PE13_44") (pintype "bidirectional"))
    )
    (net (code "32") (name "A14") (class "Default")
      (node (ref "12B") (pin "1") (pinfunction "P_1") (pintype "passive"))
      (node (ref "U$1") (pin "P45") (pinfunction "IO_L49N_D4_2_P45") (pintype "bidirectional"))
    )
    (net (code "33") (name "A14'") (class "Default")
      (node (ref "U$1") (pin "P111") (pinfunction "IO_L66N_SCP0_0_P111") (pintype "bidirectional"))
      (node (ref "U2") (pin "3") (pinfunction "A14_3") (pintype "input"))
      (node (ref "U3") (pin "45") (pinfunction "PE14_45") (pintype "bidirectional"))
    )
    (net (code "34") (name "A15") (class "Default")
      (node (ref "11B") (pin "1") (pinfunction "P_1") (pintype "passive"))
      (node (ref "U$1") (pin "P43") (pinfunction "IO_L62N_D6_2_P43") (pintype "bidirectional"))
    )
    (net (code "35") (name "A15'") (class "Default")
      (node (ref "U$1") (pin "P112") (pinfunction "IO_L66P_SCP1_0_P112") (pintype "bidirectional"))
      (node (ref "U2") (pin "31") (pinfunction "A15_31") (pintype "input"))
      (node (ref "U3") (pin "46") (pinfunction "PE15_46") (pintype "bidirectional"))
    )
    (net (code "36") (name "A16'") (class "Default")
      (node (ref "U$1") (pin "P114") (pinfunction "IO_L65N_SCP2_0_P114") (pintype "bidirectional"))
      (node (ref "U2") (pin "2") (pinfunction "A16_2") (pintype "input"))
      (node (ref "U3") (pin "48") (pinfunction "PB11_48") (pintype "bidirectional"))
    )
    (net (code "37") (name "A17'") (class "Default")
      (node (ref "U$1") (pin "P61") (pinfunction "IO_L12N_D2_MISO3_2_P61") (pintype "bidirectional"))
      (node (ref "U2") (pin "30") (pinfunction "A17_30") (pintype "input"))
      (node (ref "U3") (pin "51") (pinfunction "PB12_51") (pintype "bidirectional"))
    )
    (net (code "38") (name "A18'") (class "Default")
      (node (ref "U$1") (pin "P115") (pinfunction "IO_L65P_SCP3_0_P115") (pintype "bidirectional"))
      (node (ref "U2") (pin "1") (pinfunction "A18_1") (pintype "input"))
      (node (ref "U3") (pin "52") (pinfunction "PB13_52") (pintype "bidirectional"))
    )
    (net (code "39") (name "AMPLI_OUT") (class "Default")
      (node (ref "C14") (pin "2") (pinfunction "2_2") (pintype "passive"))
      (node (ref "R1") (pin "2") (pinfunction "2_2") (pintype "passive"))
      (node (ref "SJ1") (pin "2") (pinfunction "2_2") (pintype "passive"))
    )
    (net (code "40") (name "AMPLI_OUT'") (class "Default")
      (node (ref "J4") (pin "2") (pinfunction "2_2") (pintype "passive"))
      (node (ref "J4") (pin "3") (pinfunction "3_3") (pintype "passive"))
      (node (ref "R1") (pin "1") (pinfunction "1_1") (pintype "passive"))
    )
    (net (code "41") (name "B0") (class "Default")
      (node (ref "U$1") (pin "P116") (pinfunction "IO_L64N_SCP4_0_P116") (pintype "bidirectional"))
      (node (ref "U3") (pin "55") (pinfunction "PD8_55") (pintype "bidirectional"))
    )
    (net (code "42") (name "B1") (class "Default")
      (node (ref "U$1") (pin "P117") (pinfunction "IO_L64P_SCP5_0_P117") (pintype "bidirectional"))
      (node (ref "U3") (pin "56") (pinfunction "PD9_56") (pintype "bidirectional"))
    )
    (net (code "43") (name "B2") (class "Default")
      (node (ref "U$1") (pin "P118") (pinfunction "IO_L63N_SCP6_0_P118") (pintype "bidirectional"))
      (node (ref "U3") (pin "57") (pinfunction "PD10_57") (pintype "bidirectional"))
    )
    (net (code "44") (name "B3") (class "Default")
      (node (ref "U$1") (pin "P119") (pinfunction "IO_L63P_SCP7_0_P119") (pintype "bidirectional"))
      (node (ref "U3") (pin "58") (pinfunction "PD11_58") (pintype "bidirectional"))
    )
    (net (code "45") (name "B4") (class "Default")
      (node (ref "U$1") (pin "P120") (pinfunction "IO_L62N_VREF_0_P120") (pintype "bidirectional"))
      (node (ref "U3") (pin "59") (pinfunction "PD12_59") (pintype "bidirectional"))
    )
    (net (code "46") (name "B5") (class "Default")
      (node (ref "U$1") (pin "P121") (pinfunction "IO_L62P_0_P121") (pintype "bidirectional"))
      (node (ref "U3") (pin "60") (pinfunction "PD13_60") (pintype "bidirectional"))
    )
    (net (code "47") (name "B6") (class "Default")
      (node (ref "U$1") (pin "P123") (pinfunction "IO_L37N_GCLK12_0_P123") (pintype "bidirectional"))
      (node (ref "U3") (pin "61") (pinfunction "PD14_61") (pintype "bidirectional"))
    )
    (net (code "48") (name "B7") (class "Default")
      (node (ref "U$1") (pin "P124") (pinfunction "IO_L37P_GCLK13_0_P124") (pintype "bidirectional"))
      (node (ref "U3") (pin "62") (pinfunction "PD15_62") (pintype "bidirectional"))
    )
    (net (code "49") (name "BOOT0") (class "Default")
      (node (ref "R24") (pin "1") (pinfunction "1_1") (pintype "passive"))
      (node (ref "R30") (pin "2") (pinfunction "2_2") (pintype "passive"))
      (node (ref "U3") (pin "94") (pinfunction "BOOT0_94") (pintype "bidirectional"))
    )
    (net (code "50") (name "BRIGHT") (class "Default")
      (node (ref "R33") (pin "1") (pinfunction "1_1") (pintype "passive"))
      (node (ref "R34") (pin "1") (pinfunction "1_1") (pintype "passive"))
      (node (ref "R35") (pin "1") (pinfunction "1_1") (pintype "passive"))
      (node (ref "U$1") (pin "P11") (pinfunction "IO_L49N_3_P11") (pintype "bidirectional"))
    )
    (net (code "51") (name "CC1") (class "Default")
      (node (ref "J3") (pin "A5") (pinfunction "CC1_A5") (pintype "bidirectional"))
    )
    (net (code "52") (name "CC2") (class "Default")
      (node (ref "J3") (pin "B5") (pinfunction "CC2_B5") (pintype "bidirectional"))
    )
    (net (code "53") (name "CFG_CLK") (class "Default")
      (node (ref "U$1") (pin "P17") (pinfunction "IO_L43P_GCLK23_3_P17") (pintype "bidirectional"))
      (node (ref "U3") (pin "35") (pinfunction "PB0_35") (pintype "bidirectional"))
    )
    (net (code "54") (name "CFG_DATA") (class "Default")
      (node (ref "U$1") (pin "P15") (pinfunction "IO_L44P_GCLK21_3_P15") (pintype "bidirectional"))
      (node (ref "U3") (pin "89") (pinfunction "PB3_89") (pintype "bidirectional"))
    )
    (net (code "55") (name "CFG_RESET") (class "Default")
      (node (ref "U$1") (pin "P16") (pinfunction "IO_L43N_GCLK22_IRDY2_3_P16") (pintype "bidirectional"))
      (node (ref "U3") (pin "36") (pinfunction "PB1_36") (pintype "bidirectional"))
    )
    (net (code "56") (name "COMPOSITE") (class "Default")
      (node (ref "J2") (pin "5") (pinfunction "5_5") (pintype "passive"))
      (node (ref "R4") (pin "1") (pinfunction "1_1") (pintype "passive"))
    )
    (net (code "57") (name "CS_LLS") (class "Default")
      (node (ref "MICRO_SD1") (pin "2") (pinfunction "CD/DAT3_2") (pintype "bidirectional"))
      (node (ref "R21") (pin "2") (pinfunction "2_2") (pintype "passive"))
    )
    (net (code "58") (name "CTRL_CLK") (class "Default")
      (node (ref "U$1") (pin "P6") (pinfunction "IO_L52P_3_P6") (pintype "bidirectional"))
      (node (ref "U3") (pin "90") (pinfunction "PB4_90") (pintype "bidirectional"))
    )
    (net (code "59") (name "D0") (class "Default")
      (node (ref "4A") (pin "1") (pinfunction "P_1") (pintype "passive"))
      (node (ref "U$1") (pin "P23") (pinfunction "IO_L41N_GCLK26_3_P23") (pintype "bidirectional"))
      (node (ref "U2") (pin "13") (pinfunction "DQ0_13") (pintype "output"))
    )
    (net (code "60") (name "D1") (class "Default")
      (node (ref "5A") (pin "1") (pinfunction "P_1") (pintype "passive"))
      (node (ref "U$1") (pin "P26") (pinfunction "IO_L37N_3_P26") (pintype "bidirectional"))
      (node (ref "U2") (pin "14") (pinfunction "DQ1_14") (pintype "output"))
    )
    (net (code "61") (name "D2") (class "Default")
      (node (ref "6A") (pin "1") (pinfunction "P_1") (pintype "passive"))
      (node (ref "U$1") (pin "P27") (pinfunction "IO_L37P_3_P27") (pintype "bidirectional"))
      (node (ref "U2") (pin "15") (pinfunction "DQ2_15") (pintype "output"))
    )
    (net (code "62") (name "D3") (class "Default")
      (node (ref "9A") (pin "1") (pinfunction "P_1") (pintype "passive"))
      (node (ref "U$1") (pin "P34") (pinfunction "IO_L1N_VREF_3_P34") (pintype "bidirectional"))
      (node (ref "U2") (pin "17") (pinfunction "DQ3_17") (pintype "output"))
    )
    (net (code "63") (name "D4") (class "Default")
      (node (ref "10A") (pin "1") (pinfunction "P_1") (pintype "passive"))
      (node (ref "U$1") (pin "P39") (pinfunction "IO_L65P_INIT_B_2_P39") (pintype "bidirectional"))
      (node (ref "U2") (pin "18") (pinfunction "DQ4_18") (pintype "output"))
    )
    (net (code "64") (name "D5") (class "Default")
      (node (ref "8A") (pin "1") (pinfunction "P_1") (pintype "passive"))
      (node (ref "U$1") (pin "P32") (pinfunction "IO_L2N_3_P32") (pintype "bidirectional"))
      (node (ref "U2") (pin "19") (pinfunction "DQ5_19") (pintype "output"))
    )
    (net (code "65") (name "D6") (class "Default")
      (node (ref "7A") (pin "1") (pinfunction "P_1") (pintype "passive"))
      (node (ref "U$1") (pin "P29") (pinfunction "IO_L36N_3_P29") (pintype "bidirectional"))
      (node (ref "U2") (pin "20") (pinfunction "DQ6_20") (pintype "output"))
    )
    (net (code "66") (name "D7") (class "Default")
      (node (ref "1A") (pin "1") (pinfunction "P_1") (pintype "passive"))
      (node (ref "U$1") (pin "P21") (pinfunction "IO_L42N_GCLK24_3_P21") (pintype "bidirectional"))
      (node (ref "U2") (pin "21") (pinfunction "DQ7_21") (pintype "output"))
    )
    (net (code "67") (name "DI_LLS") (class "Default")
      (node (ref "MICRO_SD1") (pin "3") (pinfunction "CMD_3") (pintype "bidirectional"))
      (node (ref "R17") (pin "2") (pinfunction "2_2") (pintype "passive"))
    )
    (net (code "68") (name "DOWN") (class "Default")
      (node (ref "J2") (pin "2") (pinfunction "2_2") (pintype "passive"))
      (node (ref "U$1") (pin "P79") (pinfunction "IO_L47P_1_P79") (pintype "bidirectional"))
    )
    (net (code "69") (name "EN_M1_NOT") (class "Default")
      (node (ref "U$1") (pin "P140") (pinfunction "IO_L3P_0_P140") (pintype "bidirectional"))
      (node (ref "U3") (pin "25") (pinfunction "PA2_25") (pintype "bidirectional"))
    )
    (net (code "70") (name "FIRE") (class "Default")
      (node (ref "J2") (pin "6") (pinfunction "6_6") (pintype "passive"))
      (node (ref "U$1") (pin "P82") (pinfunction "IO_L45N_1_P82") (pintype "bidirectional"))
    )
    (net (code "71") (name "FLASH_CS") (class "Default")
      (node (ref "U$1") (pin "P38") (pinfunction "IO_L65N_CSO_B_2_P38") (pintype "bidirectional"))
      (node (ref "U4") (pin "1") (pinfunction "CS_1") (pintype "bidirectional"))
    )
    (net (code "72") (name "FLASH_MISO") (class "Default")
      (node (ref "U$1") (pin "P65") (pinfunction "IO_L3P_D0_DIN_MISO_MISO1_2_P65") (pintype "bidirectional"))
      (node (ref "U4") (pin "2") (pinfunction "MISO_2") (pintype "bidirectional"))
    )
    (net (code "73") (name "FLASH_MOSI") (class "Default")
      (node (ref "U$1") (pin "P64") (pinfunction "IO_L3N_MOSI_CSI_B_MISO0_2_P64") (pintype "bidirectional"))
      (node (ref "U4") (pin "5") (pinfunction "MOSI_5") (pintype "bidirectional"))
    )
    (net (code "74") (name "FLASH_SCLK") (class "Default")
      (node (ref "U$1") (pin "P70") (pinfunction "IO_L1P_CCLK_2_P70") (pintype "bidirectional"))
      (node (ref "U4") (pin "6") (pinfunction "SCK_6") (pintype "bidirectional"))
    )
    (net (code "75") (name "GET_CTRL_REG") (class "Default")
      (node (ref "U$1") (pin "P5") (pinfunction "IO_L52N_3_P5") (pintype "bidirectional"))
      (node (ref "U3") (pin "66") (pinfunction "PC9_66") (pintype "bidirectional"))
    )
    (net (code "76") (name "GET_DATA_REG") (class "Default")
      (node (ref "U$1") (pin "P2") (pinfunction "IO_L83P_3_P2") (pintype "bidirectional"))
      (node (ref "U3") (pin "78") (pinfunction "PC10_78") (pintype "bidirectional"))
    )
    (net (code "77") (name "GND") (class "Default")
      (node (ref "4B") (pin "1") (pinfunction "P_1") (pintype "passive"))
      (node (ref "5B") (pin "1") (pinfunction "P_1") (pintype "passive"))
      (node (ref "BT1") (pin "N") (pinfunction "NEG_N") (pintype "passive"))
      (node (ref "C10") (pin "2") (pinfunction "2_2") (pintype "passive"))
      (node (ref "C11") (pin "1") (pinfunction "1_1") (pintype "passive"))
      (node (ref "C12") (pin "1") (pinfunction "1_1") (pintype "passive"))
      (node (ref "C18") (pin "2") (pinfunction "2_2") (pintype "passive"))
      (node (ref "C19") (pin "2") (pinfunction "2_2") (pintype "passive"))
      (node (ref "C2") (pin "2") (pinfunction "2_2") (pintype "passive"))
      (node (ref "C22") (pin "1") (pinfunction "1_1") (pintype "passive"))
      (node (ref "C23") (pin "1") (pinfunction "1_1") (pintype "passive"))
      (node (ref "C24") (pin "2") (pinfunction "2_2") (pintype "passive"))
      (node (ref "C25") (pin "2") (pinfunction "2_2") (pintype "passive"))
      (node (ref "C26") (pin "2") (pinfunction "2_2") (pintype "passive"))
      (node (ref "C3") (pin "2") (pinfunction "2_2") (pintype "passive"))
      (node (ref "C33") (pin "2") (pinfunction "2_2") (pintype "passive"))
      (node (ref "C4") (pin "1") (pinfunction "1_1") (pintype "passive"))
      (node (ref "C5") (pin "1") (pinfunction "1_1") (pintype "passive"))
      (node (ref "C6") (pin "2") (pinfunction "2_2") (pintype "passive"))
      (node (ref "C7") (pin "2") (pinfunction "2_2") (pintype "passive"))
      (node (ref "C8") (pin "1") (pinfunction "1_1") (pintype "passive"))
      (node (ref "C9") (pin "1") (pinfunction "1_1") (pintype "passive"))
      (node (ref "IC2") (pin "1") (pinfunction "GND_1") (pintype "power_in"))
      (node (ref "IC5") (pin "1") (pinfunction "GND_1") (pintype "power_in"))
      (node (ref "J2") (pin "8") (pinfunction "8_8") (pintype "passive"))
      (node (ref "J3") (pin "A1_B12") (pinfunction "GND_A1_B12") (pintype "power_in"))
      (node (ref "J3") (pin "B1_A12") (pinfunction "GND_B1_A12") (pintype "power_in"))
      (node (ref "J3") (pin "SH1") (pinfunction "SHIELD_SH1") (pintype "passive"))
      (node (ref "J3") (pin "SH2") (pinfunction "SHIELD_SH2") (pintype "passive"))
      (node (ref "J3") (pin "SH3") (pinfunction "SHIELD_SH3") (pintype "passive"))
      (node (ref "J3") (pin "SH4") (pinfunction "SHIELD_SH4") (pintype "passive"))
      (node (ref "JP4") (pin "2") (pinfunction "2_2") (pintype "passive"))
      (node (ref "JP5") (pin "2") (pinfunction "2_2") (pintype "passive"))
      (node (ref "JP6") (pin "2") (pinfunction "2_2") (pintype "passive"))
      (node (ref "JP8") (pin "2") (pinfunction "2_2") (pintype "passive"))
      (node (ref "LED3") (pin "P1") (pinfunction "C_P1") (pintype "passive"))
      (node (ref "LED3") (pin "P2") (pinfunction "C_P2") (pintype "passive"))
      (node (ref "LED3") (pin "P3") (pinfunction "C_P3") (pintype "passive"))
      (node (ref "MICRO_SD1") (pin "6") (pinfunction "VSS_6") (pintype "power_in"))
      (node (ref "MICRO_SD1") (pin "MP1") (pinfunction "SHIELD_MP1") (pintype "power_in"))
      (node (ref "MICRO_SD1") (pin "MP2") (pinfunction "SHIELD_MP2") (pintype "power_in"))
      (node (ref "MICRO_SD1") (pin "MP3") (pinfunction "SHIELD_MP3") (pintype "power_in"))
      (node (ref "MICRO_SD1") (pin "MP4") (pinfunction "SHIELD_MP4") (pintype "power_in"))
      (node (ref "R19") (pin "2") (pinfunction "2_2") (pintype "passive"))
      (node (ref "R25") (pin "1") (pinfunction "1_1") (pintype "passive"))
      (node (ref "R27") (pin "2") (pinfunction "2_2") (pintype "passive"))
      (node (ref "R28") (pin "2") (pinfunction "2_2") (pintype "passive"))
      (node (ref "R30") (pin "1") (pinfunction "1_1") (pintype "passive"))
      (node (ref "S1") (pin "1") (pinfunction "P_1") (pintype "passive"))
      (node (ref "SJ2") (pin "1") (pinfunction "1_1") (pintype "passive"))
      (node (ref "U$1") (pin "P108") (pinfunction "GND_P108") (pintype "bidirectional"))
      (node (ref "U$1") (pin "P113") (pinfunction "GND_P113") (pintype "bidirectional"))
      (node (ref "U$1") (pin "P13") (pinfunction "GND_P13") (pintype "bidirectional"))
      (node (ref "U$1") (pin "P130") (pinfunction "GND_P130") (pintype "bidirectional"))
      (node (ref "U$1") (pin "P136") (pinfunction "GND_P136") (pintype "bidirectional"))
      (node (ref "U$1") (pin "P25") (pinfunction "GND_P25") (pintype "bidirectional"))
      (node (ref "U$1") (pin "P3") (pinfunction "GND_P3") (pintype "bidirectional"))
      (node (ref "U$1") (pin "P49") (pinfunction "GND_P49") (pintype "bidirectional"))
      (node (ref "U$1") (pin "P54") (pinfunction "GND_P54") (pintype "bidirectional"))
      (node (ref "U$1") (pin "P68") (pinfunction "GND_P68") (pintype "bidirectional"))
      (node (ref "U$1") (pin "P73") (pinfunction "SUSPEND_P73") (pintype "bidirectional"))
      (node (ref "U$1") (pin "P77") (pinfunction "GND_P77") (pintype "bidirectional"))
      (node (ref "U$1") (pin "P91") (pinfunction "GND_P91") (pintype "bidirectional"))
      (node (ref "U$1") (pin "P96") (pinfunction "GND_P96") (pintype "bidirectional"))
      (node (ref "U1") (pin "13") (pinfunction "DGND_13") (pintype "passive"))
      (node (ref "U1") (pin "2") (pinfunction "AGND_2") (pintype "passive"))
      (node (ref "U2") (pin "16") (pinfunction "VSS_16") (pintype "output"))
      (node (ref "U2") (pin "22") (pinfunction "CE_22") (pintype "input"))
      (node (ref "U3") (pin "10") (pinfunction "VSS_10") (pintype "bidirectional"))
      (node (ref "U3") (pin "20") (pinfunction "VSSA_20") (pintype "bidirectional"))
      (node (ref "U3") (pin "27") (pinfunction "VSS_27") (pintype "bidirectional"))
      (node (ref "U3") (pin "74") (pinfunction "VSS_74") (pintype "bidirectional"))
      (node (ref "U3") (pin "99") (pinfunction "VSS_99") (pintype "bidirectional"))
      (node (ref "U4") (pin "4") (pinfunction "GND_4") (pintype "power_in"))
      (node (ref "U5") (pin "7") (pinfunction "GND_7") (pintype "power_in"))
    )
    (net (code "78") (name "HSYNC") (class "Default")
      (node (ref "U$1") (pin "P10") (pinfunction "IO_L50P_3_P10") (pintype "bidirectional"))
      (node (ref "U1") (pin "16") (pinfunction "HSYNC_16") (pintype "input"))
    )
    (net (code "79") (name "LEDB") (class "Default")
      (node (ref "R3") (pin "1") (pinfunction "1_1") (pintype "passive"))
      (node (ref "U3") (pin "64") (pinfunction "PC7_64") (pintype "bidirectional"))
    )
    (net (code "80") (name "LEDG") (class "Default")
      (node (ref "R13") (pin "1") (pinfunction "1_1") (pintype "passive"))
      (node (ref "U3") (pin "63") (pinfunction "PC6_63") (pintype "bidirectional"))
    )
    (net (code "81") (name "LEDR") (class "Default")
      (node (ref "R2") (pin "1") (pinfunction "1_1") (pintype "passive"))
      (node (ref "U3") (pin "65") (pinfunction "PC8_65") (pintype "bidirectional"))
    )
    (net (code "82") (name "LEFT") (class "Default")
      (node (ref "J2") (pin "3") (pinfunction "3_3") (pintype "passive"))
      (node (ref "U$1") (pin "P80") (pinfunction "IO_L46N_1_P80") (pintype "bidirectional"))
    )
    (net (code "83") (name "LE_IL") (class "Default")
      (node (ref "U$1") (pin "P14") (pinfunction "IO_L44N_GCLK20_3_P14") (pintype "bidirectional"))
      (node (ref "U3") (pin "7") (pinfunction "PC13_7") (pintype "bidirectional"))
    )
    (net (code "84") (name "MISO") (class "Default")
      (node (ref "R20") (pin "1") (pinfunction "1_1") (pintype "passive"))
      (node (ref "U3") (pin "31") (pinfunction "PA6_31") (pintype "bidirectional"))
    )
    (net (code "85") (name "MOSI") (class "Default")
      (node (ref "R17") (pin "1") (pinfunction "1_1") (pintype "passive"))
      (node (ref "U3") (pin "32") (pinfunction "PA7_32") (pintype "bidirectional"))
    )
    (net (code "86") (name "Net-(1B-P)") (class "Default")
      (node (ref "1B") (pin "1") (pinfunction "P_1") (pintype "passive"))
      (node (ref "D4") (pin "A") (pinfunction "A_A") (pintype "passive"))
    )
    (net (code "87") (name "Net-(BT1-POS)") (class "Default")
      (node (ref "BT1") (pin "P") (pinfunction "POS_P") (pintype "passive"))
      (node (ref "D3") (pin "2") (pinfunction "A2_2") (pintype "passive"))
      (node (ref "U3") (pin "16") (pinfunction "PC1_16") (pintype "bidirectional"))
    )
    (net (code "88") (name "Net-(C1-Pad2)") (class "Default")
      (node (ref "C1") (pin "2") (pinfunction "2_2") (pintype "passive"))
      (node (ref "R4") (pin "2") (pinfunction "2_2") (pintype "passive"))
    )
    (net (code "89") (name "Net-(C9-Pad2)") (class "Default")
      (node (ref "C9") (pin "2") (pinfunction "2_2") (pintype "passive"))
      (node (ref "R5") (pin "2") (pinfunction "2_2") (pintype "passive"))
    )
    (net (code "90") (name "Net-(C13-Pad2)") (class "Default")
      (node (ref "C13") (pin "2") (pinfunction "2_2") (pintype "passive"))
      (node (ref "R6") (pin "2") (pinfunction "2_2") (pintype "passive"))
    )
    (net (code "91") (name "Net-(D3-CC)") (class "Default")
      (node (ref "D3") (pin "3") (pinfunction "CC_3") (pintype "passive"))
      (node (ref "U3") (pin "6") (pinfunction "VBAT_6") (pintype "bidirectional"))
    )
    (net (code "92") (name "Net-(J3-DN1)") (class "Default")
      (node (ref "J3") (pin "A7") (pinfunction "DN1_A7") (pintype "bidirectional"))
      (node (ref "J3") (pin "B7") (pinfunction "DN2_B7") (pintype "bidirectional"))
      (node (ref "R26") (pin "1") (pinfunction "1_1") (pintype "passive"))
    )
    (net (code "93") (name "Net-(J3-DP1)") (class "Default")
      (node (ref "J3") (pin "A6") (pinfunction "DP1_A6") (pintype "bidirectional"))
      (node (ref "J3") (pin "B6") (pinfunction "DP2_B6") (pintype "bidirectional"))
      (node (ref "R22") (pin "1") (pinfunction "1_1") (pintype "passive"))
      (node (ref "R23") (pin "1") (pinfunction "1_1") (pintype "passive"))
    )
    (net (code "94") (name "Net-(J4-Pad4)") (class "Default")
      (node (ref "J4") (pin "4") (pinfunction "4_4") (pintype "passive"))
      (node (ref "JP1") (pin "2") (pinfunction "2_2") (pintype "passive"))
    )
    (net (code "95") (name "Net-(J4-Pad5)") (class "Default")
      (node (ref "J4") (pin "5") (pinfunction "5_5") (pintype "passive"))
      (node (ref "JP1") (pin "1") (pinfunction "1_1") (pintype "passive"))
    )
    (net (code "96") (name "Net-(JP7-Pad1)") (class "Default")
      (node (ref "JP7") (pin "1") (pinfunction "1_1") (pintype "passive"))
      (node (ref "R24") (pin "2") (pinfunction "2_2") (pintype "passive"))
    )
    (net (code "97") (name "Net-(JP7-Pad3)") (class "Default")
      (node (ref "JP7") (pin "3") (pinfunction "3_3") (pintype "passive"))
      (node (ref "R16") (pin "1") (pinfunction "1_1") (pintype "passive"))
    )
    (net (code "98") (name "Net-(LED2-PadA)") (class "Default")
      (node (ref "LED2") (pin "A") (pinfunction "A_A") (pintype "passive"))
      (node (ref "R11") (pin "2") (pinfunction "2_2") (pintype "passive"))
    )
    (net (code "99") (name "Net-(LED3A-A)") (class "Default")
      (node (ref "LED3") (pin "P6") (pinfunction "A_P6") (pintype "passive"))
      (node (ref "R3") (pin "2") (pinfunction "2_2") (pintype "passive"))
    )
    (net (code "100") (name "Net-(LED3B-A)") (class "Default")
      (node (ref "LED3") (pin "P5") (pinfunction "A_P5") (pintype "passive"))
      (node (ref "R13") (pin "2") (pinfunction "2_2") (pintype "passive"))
    )
    (net (code "101") (name "Net-(LED3C-A)") (class "Default")
      (node (ref "LED3") (pin "P4") (pinfunction "A_P4") (pintype "passive"))
      (node (ref "R2") (pin "2") (pinfunction "2_2") (pintype "passive"))
    )
    (net (code "102") (name "Net-(MICRO_SD1-DAT0)") (class "Default")
      (node (ref "MICRO_SD1") (pin "7") (pinfunction "DAT0_7") (pintype "bidirectional"))
      (node (ref "R20") (pin "2") (pinfunction "2_2") (pintype "passive"))
    )
    (net (code "103") (name "Net-(Q3-2)") (class "Default")
      (node (ref "C12") (pin "2") (pinfunction "2_2") (pintype "passive"))
      (node (ref "Q3") (pin "3") (pinfunction "2_3") (pintype "passive"))
      (node (ref "R14") (pin "2") (pinfunction "2_2") (pintype "passive"))
      (node (ref "U3") (pin "13") (pinfunction "PH1_13") (pintype "bidirectional"))
    )
    (net (code "104") (name "Net-(R10-Pad2)") (class "Default")
      (node (ref "R10") (pin "2") (pinfunction "2_2") (pintype "passive"))
      (node (ref "R32") (pin "2") (pinfunction "2_2") (pintype "passive"))
      (node (ref "R35") (pin "2") (pinfunction "2_2") (pintype "passive"))
    )
    (net (code "105") (name "Net-(R29-Pad2)") (class "Default")
      (node (ref "R29") (pin "2") (pinfunction "2_2") (pintype "passive"))
      (node (ref "R33") (pin "2") (pinfunction "2_2") (pintype "passive"))
      (node (ref "R8") (pin "2") (pinfunction "2_2") (pintype "passive"))
    )
    (net (code "106") (name "Net-(R31-Pad2)") (class "Default")
      (node (ref "R31") (pin "2") (pinfunction "2_2") (pintype "passive"))
      (node (ref "R34") (pin "2") (pinfunction "2_2") (pintype "passive"))
      (node (ref "R9") (pin "2") (pinfunction "2_2") (pintype "passive"))
    )
    (net (code "107") (name "Net-(U$1-PROGRAM_B_2)") (class "Default")
      (node (ref "R12") (pin "2") (pinfunction "2_2") (pintype "passive"))
      (node (ref "U$1") (pin "P37") (pinfunction "PROGRAM_B_2_P37") (pintype "bidirectional"))
    )
    (net (code "108") (name "Net-(U1-BIN)") (class "Default")
      (node (ref "R28") (pin "1") (pinfunction "1_1") (pintype "passive"))
      (node (ref "R8") (pin "1") (pinfunction "1_1") (pintype "passive"))
      (node (ref "U1") (pin "8") (pinfunction "BIN_8") (pintype "input"))
    )
    (net (code "109") (name "Net-(U1-COMP)") (class "Default")
      (node (ref "C1") (pin "1") (pinfunction "1_1") (pintype "passive"))
      (node (ref "U1") (pin "10") (pinfunction "COMP_10") (pintype "output"))
    )
    (net (code "110") (name "Net-(U1-GIN)") (class "Default")
      (node (ref "R27") (pin "1") (pinfunction "1_1") (pintype "passive"))
      (node (ref "R9") (pin "1") (pinfunction "1_1") (pintype "passive"))
      (node (ref "U1") (pin "7") (pinfunction "GIN_7") (pintype "input"))
    )
    (net (code "111") (name "Net-(U1-RIN)") (class "Default")
      (node (ref "R10") (pin "1") (pinfunction "1_1") (pintype "passive"))
      (node (ref "R19") (pin "1") (pinfunction "1_1") (pintype "passive"))
      (node (ref "U1") (pin "6") (pinfunction "RIN_6") (pintype "input"))
    )
    (net (code "112") (name "Net-(U3-PC14)") (class "Default")
      (node (ref "C22") (pin "2") (pinfunction "2_2") (pintype "passive"))
      (node (ref "Q4") (pin "2") (pinfunction "2_2") (pintype "passive"))
      (node (ref "U3") (pin "8") (pinfunction "PC14_8") (pintype "bidirectional"))
    )
    (net (code "113") (name "Net-(U3-PC15)") (class "Default")
      (node (ref "C23") (pin "2") (pinfunction "2_2") (pintype "passive"))
      (node (ref "Q4") (pin "1") (pinfunction "1_1") (pintype "passive"))
      (node (ref "U3") (pin "9") (pinfunction "PC15_9") (pintype "bidirectional"))
    )
    (net (code "114") (name "Net-(U3-PH0)") (class "Default")
      (node (ref "C11") (pin "2") (pinfunction "2_2") (pintype "passive"))
      (node (ref "Q3") (pin "1") (pinfunction "1_1") (pintype "passive"))
      (node (ref "R14") (pin "1") (pinfunction "1_1") (pintype "passive"))
      (node (ref "U3") (pin "12") (pinfunction "PH0_12") (pintype "bidirectional"))
    )
    (net (code "115") (name "Net-(U3-VCAP_1)") (class "Default")
      (node (ref "C10") (pin "1") (pinfunction "1_1") (pintype "passive"))
      (node (ref "U3") (pin "49") (pinfunction "VCAP_1_49") (pintype "bidirectional"))
    )
    (net (code "116") (name "Net-(U3-VCAP_2)") (class "Default")
      (node (ref "C7") (pin "1") (pinfunction "1_1") (pintype "passive"))
      (node (ref "U3") (pin "73") (pinfunction "VCAP_2_73") (pintype "bidirectional"))
    )
    (net (code "117") (name "Net-(U5-IN+)") (class "Default")
      (node (ref "R6") (pin "1") (pinfunction "1_1") (pintype "passive"))
      (node (ref "U5") (pin "3") (pinfunction "IN+_3") (pintype "input"))
    )
    (net (code "118") (name "Net-(U5-IN-)") (class "Default")
      (node (ref "R5") (pin "1") (pinfunction "1_1") (pintype "passive"))
      (node (ref "U5") (pin "4") (pinfunction "IN-_4") (pintype "input"))
    )
    (net (code "119") (name "Net-(U5-VO+)") (class "Default")
      (node (ref "C14") (pin "1") (pinfunction "1_1") (pintype "passive"))
      (node (ref "U5") (pin "5") (pinfunction "VO+_5") (pintype "output"))
    )
    (net (code "120") (name "Net-(U5-VO-)") (class "Default")
      (node (ref "J4") (pin "1") (pinfunction "1_1") (pintype "passive"))
      (node (ref "SJ2") (pin "2") (pinfunction "2_2") (pintype "passive"))
      (node (ref "U5") (pin "8") (pinfunction "VO-_8") (pintype "output"))
    )
    (net (code "121") (name "Net-(U5-~{SD})") (class "Default")
      (node (ref "R7") (pin "1") (pinfunction "1_1") (pintype "passive"))
      (node (ref "U5") (pin "1") (pinfunction "~{SD}_1") (pintype "input"))
    )
    (net (code "122") (name "O0") (class "Default")
      (node (ref "U$1") (pin "P126") (pinfunction "IO_L36N_GCLK14_0_P126") (pintype "bidirectional"))
      (node (ref "U3") (pin "81") (pinfunction "PD0_81") (pintype "bidirectional"))
    )
    (net (code "123") (name "O1") (class "Default")
      (node (ref "U$1") (pin "P127") (pinfunction "IO_L36P_GCLK15_0_P127") (pintype "bidirectional"))
      (node (ref "U3") (pin "82") (pinfunction "PD1_82") (pintype "bidirectional"))
    )
    (net (code "124") (name "O2") (class "Default")
      (node (ref "U$1") (pin "P131") (pinfunction "IO_L35N_GCLK16_0_P131") (pintype "bidirectional"))
      (node (ref "U3") (pin "83") (pinfunction "PD2_83") (pintype "bidirectional"))
    )
    (net (code "125") (name "O3") (class "Default")
      (node (ref "U$1") (pin "P132") (pinfunction "IO_L35P_GCLK17_0_P132") (pintype "bidirectional"))
      (node (ref "U3") (pin "84") (pinfunction "PD3_84") (pintype "bidirectional"))
    )
    (net (code "126") (name "O4") (class "Default")
      (node (ref "U$1") (pin "P133") (pinfunction "IO_L34N_GCLK18_0_P133") (pintype "bidirectional"))
      (node (ref "U3") (pin "85") (pinfunction "PD4_85") (pintype "bidirectional"))
    )
    (net (code "127") (name "O5") (class "Default")
      (node (ref "U$1") (pin "P134") (pinfunction "IO_L34P_GCLK19_0_P134") (pintype "bidirectional"))
      (node (ref "U3") (pin "86") (pinfunction "PD5_86") (pintype "bidirectional"))
    )
    (net (code "128") (name "O6") (class "Default")
      (node (ref "U$1") (pin "P137") (pinfunction "IO_L4N_0_P137") (pintype "bidirectional"))
      (node (ref "U3") (pin "87") (pinfunction "PD6_87") (pintype "bidirectional"))
    )
    (net (code "129") (name "O7") (class "Default")
      (node (ref "U$1") (pin "P138") (pinfunction "IO_L4P_0_P138") (pintype "bidirectional"))
      (node (ref "U3") (pin "88") (pinfunction "PD7_88") (pintype "bidirectional"))
    )
    (net (code "130") (name "PA11{slash}USB_DN") (class "Default")
      (node (ref "R26") (pin "2") (pinfunction "2_2") (pintype "passive"))
      (node (ref "U3") (pin "70") (pinfunction "PA11_70") (pintype "bidirectional"))
    )
    (net (code "131") (name "PA12{slash}USB_DP") (class "Default")
      (node (ref "R23") (pin "2") (pinfunction "2_2") (pintype "passive"))
      (node (ref "U3") (pin "71") (pinfunction "PA12_71") (pintype "bidirectional"))
    )
    (net (code "132") (name "PA13{slash}JTMS{slash}SWDIO") (class "Default")
      (node (ref "JP8") (pin "1") (pinfunction "1_1") (pintype "passive"))
      (node (ref "U3") (pin "72") (pinfunction "PA13_72") (pintype "bidirectional"))
    )
    (net (code "133") (name "PA14{slash}JTCK{slash}SWCLK") (class "Default")
      (node (ref "JP8") (pin "3") (pinfunction "3_3") (pintype "passive"))
      (node (ref "U3") (pin "76") (pinfunction "PA14_76") (pintype "bidirectional"))
    )
    (net (code "134") (name "PAGE_A8") (class "Default")
      (node (ref "U$1") (pin "P143") (pinfunction "IO_L1N_VREF_0_P143") (pintype "bidirectional"))
      (node (ref "U3") (pin "24") (pinfunction "PA1_24") (pintype "bidirectional"))
    )
    (net (code "135") (name "PAL-NTSC") (class "Default")
      (node (ref "U$1") (pin "P22") (pinfunction "IO_L42P_GCLK25_TRDY2_3_P22") (pintype "bidirectional"))
      (node (ref "U1") (pin "1") (pinfunction "STND_1") (pintype "input"))
      (node (ref "U3") (pin "17") (pinfunction "PC2_17") (pintype "bidirectional"))
    )
    (net (code "136") (name "PB2{slash}BOOT1") (class "Default")
      (node (ref "R16") (pin "2") (pinfunction "2_2") (pintype "passive"))
      (node (ref "R25") (pin "2") (pinfunction "2_2") (pintype "passive"))
      (node (ref "U3") (pin "37") (pinfunction "PB2_37") (pintype "bidirectional"))
    )
    (net (code "137") (name "PS2_CLOCK") (class "Default")
      (node (ref "JP6") (pin "3") (pinfunction "3_3") (pintype "passive"))
      (node (ref "U3") (pin "80") (pinfunction "PC12_80") (pintype "bidirectional"))
    )
    (net (code "138") (name "PS2_DATA") (class "Default")
      (node (ref "JP6") (pin "4") (pinfunction "4_4") (pintype "passive"))
      (node (ref "U3") (pin "79") (pinfunction "PC11_79") (pintype "bidirectional"))
    )
    (net (code "139") (name "RESET") (class "Default")
      (node (ref "C5") (pin "2") (pinfunction "2_2") (pintype "passive"))
      (node (ref "D1") (pin "A") (pinfunction "A_A") (pintype "passive"))
      (node (ref "R15") (pin "1") (pinfunction "1_1") (pintype "passive"))
      (node (ref "S1") (pin "2") (pinfunction "S_2") (pintype "passive"))
      (node (ref "U3") (pin "14") (pinfunction "NRST_14") (pintype "bidirectional"))
    )
    (net (code "140") (name "RIGHT") (class "Default")
      (node (ref "J2") (pin "4") (pinfunction "4_4") (pintype "passive"))
      (node (ref "U$1") (pin "P81") (pinfunction "IO_L46P_1_P81") (pintype "bidirectional"))
    )
    (net (code "141") (name "ROM_WR_EN") (class "Default")
      (node (ref "U$1") (pin "P142") (pinfunction "IO_L2P_0_P142") (pintype "bidirectional"))
      (node (ref "U3") (pin "67") (pinfunction "PA8_67") (pintype "bidirectional"))
    )
    (net (code "142") (name "RST_CTRL_REG") (class "Default")
      (node (ref "U$1") (pin "P1") (pinfunction "IO_L83N_VREF_3_P1") (pintype "bidirectional"))
      (node (ref "U3") (pin "53") (pinfunction "PB14_53") (pintype "bidirectional"))
    )
    (net (code "143") (name "RST_DATA_REG") (class "Default")
      (node (ref "U$1") (pin "P144") (pinfunction "IO_L1P_HSWAPEN_0_P144") (pintype "bidirectional"))
      (node (ref "U3") (pin "91") (pinfunction "PB5_91") (pintype "bidirectional"))
    )
    (net (code "144") (name "SCK_LLS") (class "Default")
      (node (ref "MICRO_SD1") (pin "5") (pinfunction "CLK_5") (pintype "bidirectional"))
      (node (ref "R18") (pin "2") (pinfunction "2_2") (pintype "passive"))
    )
    (net (code "145") (name "SCL") (class "Default")
      (node (ref "U3") (pin "92") (pinfunction "PB6_92") (pintype "bidirectional"))
    )
    (net (code "146") (name "SCLK") (class "Default")
      (node (ref "R18") (pin "1") (pinfunction "1_1") (pintype "passive"))
      (node (ref "U3") (pin "30") (pinfunction "PA5_30") (pintype "bidirectional"))
    )
    (net (code "147") (name "SDA") (class "Default")
      (node (ref "U3") (pin "93") (pinfunction "PB7_93") (pintype "bidirectional"))
    )
    (net (code "148") (name "SD_LED") (class "Default")
      (node (ref "LED2") (pin "C") (pinfunction "C_C") (pintype "passive"))
      (node (ref "U3") (pin "15") (pinfunction "PC0_15") (pintype "bidirectional"))
    )
    (net (code "149") (name "SEL_128CHARS") (class "Default")
      (node (ref "U$1") (pin "P141") (pinfunction "IO_L2N_0_P141") (pintype "bidirectional"))
      (node (ref "U3") (pin "77") (pinfunction "PA15_77") (pintype "bidirectional"))
    )
    (net (code "150") (name "SOUND") (class "Default")
      (node (ref "C13") (pin "1") (pinfunction "1_1") (pintype "passive"))
      (node (ref "SJ1") (pin "1") (pinfunction "1_1") (pintype "passive"))
      (node (ref "U3") (pin "29") (pinfunction "PA4_29") (pintype "bidirectional"))
    )
    (net (code "151") (name "SPARE") (class "Default")
      (node (ref "U$1") (pin "P75") (pinfunction "IO_L74P_AWAKE_1_P75") (pintype "bidirectional"))
    )
    (net (code "152") (name "SS_SD") (class "Default")
      (node (ref "R21") (pin "1") (pinfunction "1_1") (pintype "passive"))
      (node (ref "U3") (pin "54") (pinfunction "PB15_54") (pintype "bidirectional"))
    )
    (net (code "153") (name "TCK") (class "Default")
      (node (ref "JP3") (pin "1") (pinfunction "1_1") (pintype "passive"))
      (node (ref "U$1") (pin "P109") (pinfunction "TCK_P109") (pintype "bidirectional"))
    )
    (net (code "154") (name "TDI") (class "Default")
      (node (ref "JP3") (pin "3") (pinfunction "3_3") (pintype "passive"))
      (node (ref "U$1") (pin "P110") (pinfunction "TDI_P110") (pintype "bidirectional"))
    )
    (net (code "155") (name "TDO") (class "Default")
      (node (ref "JP3") (pin "2") (pinfunction "2_2") (pintype "passive"))
      (node (ref "U$1") (pin "P106") (pinfunction "TDO_P106") (pintype "bidirectional"))
    )
    (net (code "156") (name "TMS") (class "Default")
      (node (ref "JP3") (pin "4") (pinfunction "4_4") (pintype "passive"))
      (node (ref "U$1") (pin "P107") (pinfunction "TMS_P107") (pintype "bidirectional"))
    )
    (net (code "157") (name "UART_RX") (class "Default")
      (node (ref "JP4") (pin "3") (pinfunction "3_3") (pintype "passive"))
      (node (ref "U3") (pin "69") (pinfunction "PA10_69") (pintype "bidirectional"))
    )
    (net (code "158") (name "UART_TX") (class "Default")
      (node (ref "JP4") (pin "4") (pinfunction "4_4") (pintype "passive"))
      (node (ref "U3") (pin "68") (pinfunction "PA9_68") (pintype "bidirectional"))
    )
    (net (code "159") (name "UP") (class "Default")
      (node (ref "J2") (pin "1") (pinfunction "1_1") (pintype "passive"))
      (node (ref "U$1") (pin "P78") (pinfunction "IO_L47N_1_P78") (pintype "bidirectional"))
    )
    (net (code "160") (name "VCC") (class "Default")
      (node (ref "23B") (pin "1") (pinfunction "P_1") (pintype "passive"))
      (node (ref "2A") (pin "1") (pinfunction "P_1") (pintype "passive"))
      (node (ref "C3") (pin "1") (pinfunction "1_1") (pintype "passive"))
      (node (ref "C8") (pin "2") (pinfunction "2_2") (pintype "passive"))
      (node (ref "D1") (pin "C") (pinfunction "C_C") (pintype "passive"))
      (node (ref "D2") (pin "C") (pinfunction "C_C") (pintype "passive"))
      (node (ref "D4") (pin "C") (pinfunction "C_C") (pintype "passive"))
      (node (ref "IC2") (pin "3") (pinfunction "VIN_3") (pintype "input"))
      (node (ref "IC5") (pin "3") (pinfunction "VIN_3") (pintype "input"))
      (node (ref "JP4") (pin "1") (pinfunction "1_1") (pintype "passive"))
      (node (ref "JP6") (pin "1") (pinfunction "1_1") (pintype "passive"))
      (node (ref "R11") (pin "1") (pinfunction "1_1") (pintype "passive"))
      (node (ref "R15") (pin "2") (pinfunction "2_2") (pintype "passive"))
      (node (ref "R22") (pin "2") (pinfunction "2_2") (pintype "passive"))
      (node (ref "R7") (pin "2") (pinfunction "2_2") (pintype "passive"))
      (node (ref "U1") (pin "12") (pinfunction "SELECT_12") (pintype "input"))
      (node (ref "U1") (pin "14") (pinfunction "DPOS_14") (pintype "power_in"))
      (node (ref "U1") (pin "15") (pinfunction "VSYNC_15") (pintype "input"))
      (node (ref "U1") (pin "4") (pinfunction "APOS_4") (pintype "power_in"))
      (node (ref "U1") (pin "5") (pinfunction "ENCD_5") (pintype "input"))
      (node (ref "U2") (pin "32") (pinfunction "VCC_32") (pintype "power_in"))
      (node (ref "U5") (pin "6") (pinfunction "VDD_6") (pintype "power_in"))
    )
    (net (code "161") (name "VCC_USB") (class "Default")
      (node (ref "D2") (pin "A") (pinfunction "A_A") (pintype "passive"))
      (node (ref "J3") (pin "A4_B9") (pinfunction "VBUS_A4_B9") (pintype "power_in"))
      (node (ref "J3") (pin "B4_A9") (pinfunction "VBUS_B4_A9") (pintype "power_in"))
    )
    (net (code "162") (name "VID_CLK") (class "Default")
      (node (ref "U$1") (pin "P105") (pinfunction "IO_L1P_1_P105") (pintype "bidirectional"))
      (node (ref "U1") (pin "3") (pinfunction "FIN_3") (pintype "input"))
    )
    (net (code "163") (name "V_BLUE") (class "Default")
      (node (ref "R29") (pin "1") (pinfunction "1_1") (pintype "passive"))
      (node (ref "U$1") (pin "P9") (pinfunction "IO_L50N_3_P9") (pintype "bidirectional"))
    )
    (net (code "164") (name "V_GREEN") (class "Default")
      (node (ref "R31") (pin "1") (pinfunction "1_1") (pintype "passive"))
      (node (ref "U$1") (pin "P8") (pinfunction "IO_L51P_3_P8") (pintype "bidirectional"))
    )
    (net (code "165") (name "V_RED") (class "Default")
      (node (ref "R32") (pin "1") (pinfunction "1_1") (pintype "passive"))
      (node (ref "U$1") (pin "P7") (pinfunction "IO_L51N_3_P7") (pintype "bidirectional"))
    )
    (net (code "166") (name "unconnected-(J2-Pad7)") (class "Default")
      (node (ref "J2") (pin "7") (pinfunction "7_7") (pintype "passive"))
    )
    (net (code "167") (name "unconnected-(J2-Pad9)") (class "Default")
      (node (ref "J2") (pin "9") (pinfunction "9_9") (pintype "passive"))
    )
    (net (code "168") (name "unconnected-(MICRO_SD1-CD-PadCD1)") (class "Default")
      (node (ref "MICRO_SD1") (pin "CD1") (pinfunction "CD_CD1") (pintype "passive"))
    )
    (net (code "169") (name "unconnected-(MICRO_SD1-DAT1-Pad8)") (class "Default")
      (node (ref "MICRO_SD1") (pin "8") (pinfunction "DAT1_8") (pintype "bidirectional"))
    )
    (net (code "170") (name "unconnected-(MICRO_SD1-DAT2-Pad1)") (class "Default")
      (node (ref "MICRO_SD1") (pin "1") (pinfunction "DAT2_1") (pintype "bidirectional"))
    )
    (net (code "171") (name "unconnected-(U$1-CMPCS_B_2-PadP72)") (class "Default")
      (node (ref "U$1") (pin "P72") (pinfunction "CMPCS_B_2_P72") (pintype "bidirectional"))
    )
    (net (code "172") (name "unconnected-(U$1-DONE_2-PadP71)") (class "Default")
      (node (ref "U$1") (pin "P71") (pinfunction "DONE_2_P71") (pintype "bidirectional"))
    )
    (net (code "173") (name "unconnected-(U1-CRMA-Pad9)") (class "Default")
      (node (ref "U1") (pin "9") (pinfunction "CRMA_9") (pintype "output"))
    )
    (net (code "174") (name "unconnected-(U1-LUMA-Pad11)") (class "Default")
      (node (ref "U1") (pin "11") (pinfunction "LUMA_11") (pintype "output"))
    )
    (net (code "175") (name "unconnected-(U3-PB8-Pad95)") (class "Default")
      (node (ref "U3") (pin "95") (pinfunction "PB8_95") (pintype "bidirectional"))
    )
    (net (code "176") (name "unconnected-(U3-PC3-Pad18)") (class "Default")
      (node (ref "U3") (pin "18") (pinfunction "PC3_18") (pintype "bidirectional"))
    )
    (net (code "177") (name "unconnected-(U3-PC4-Pad33)") (class "Default")
      (node (ref "U3") (pin "33") (pinfunction "PC4_33") (pintype "bidirectional"))
    )
    (net (code "178") (name "unconnected-(U3-PC5-Pad34)") (class "Default")
      (node (ref "U3") (pin "34") (pinfunction "PC5_34") (pintype "bidirectional"))
    )
    (net (code "179") (name "unconnected-(U5-NC-Pad2)") (class "Default")
      (node (ref "U5") (pin "2") (pinfunction "NC_2") (pintype "no_connect"))
    )
    (net (code "180") (name "{slash}BUSAK") (class "Default")
      (node (ref "18A") (pin "1") (pinfunction "P_1") (pintype "passive"))
    )
    (net (code "181") (name "{slash}BUSRQ") (class "Default")
      (node (ref "20A") (pin "1") (pinfunction "P_1") (pintype "passive"))
    )
    (net (code "182") (name "{slash}CLOCK") (class "Default")
      (node (ref "6B") (pin "1") (pinfunction "P_1") (pintype "passive"))
      (node (ref "U$1") (pin "P24") (pinfunction "IO_L41P_GCLK27_3_P24") (pintype "bidirectional"))
    )
    (net (code "183") (name "{slash}HALT") (class "Default")
      (node (ref "13A") (pin "1") (pinfunction "P_1") (pintype "passive"))
      (node (ref "U$1") (pin "P46") (pinfunction "IO_L49P_D3_2_P46") (pintype "bidirectional"))
    )
    (net (code "184") (name "{slash}IORQ") (class "Default")
      (node (ref "15A") (pin "1") (pinfunction "P_1") (pintype "passive"))
      (node (ref "U$1") (pin "P51") (pinfunction "IO_L31P_GCLK31_D14_2_P51") (pintype "bidirectional"))
    )
    (net (code "185") (name "{slash}M1") (class "Default")
      (node (ref "22A") (pin "1") (pinfunction "P_1") (pintype "passive"))
      (node (ref "U$1") (pin "P67") (pinfunction "IO_L2P_CMPCLK_2_P67") (pintype "bidirectional"))
    )
    (net (code "186") (name "{slash}MEM_OE") (class "Default")
      (node (ref "U$1") (pin "P92") (pinfunction "IO_L41N_GCLK8_1_P92") (pintype "bidirectional"))
      (node (ref "U2") (pin "24") (pinfunction "OE_24") (pintype "input"))
    )
    (net (code "187") (name "{slash}MREQ") (class "Default")
      (node (ref "14A") (pin "1") (pinfunction "P_1") (pintype "passive"))
      (node (ref "U$1") (pin "P48") (pinfunction "IO_L48P_D7_2_P48") (pintype "bidirectional"))
    )
    (net (code "188") (name "{slash}NMI") (class "Default")
      (node (ref "12A") (pin "1") (pinfunction "P_1") (pintype "passive"))
      (node (ref "U$1") (pin "P44") (pinfunction "IO_L62P_D5_2_P44") (pintype "bidirectional"))
    )
    (net (code "189") (name "{slash}OE_OL") (class "Default")
      (node (ref "U$1") (pin "P12") (pinfunction "IO_L49P_3_P12") (pintype "bidirectional"))
      (node (ref "U3") (pin "47") (pinfunction "PB10_47") (pintype "bidirectional"))
    )
    (net (code "190") (name "{slash}RD") (class "Default")
      (node (ref "16A") (pin "1") (pinfunction "P_1") (pintype "passive"))
      (node (ref "U$1") (pin "P56") (pinfunction "IO_L30P_GCLK1_D13_2_P56") (pintype "bidirectional"))
    )
    (net (code "191") (name "{slash}RESET") (class "Default")
      (node (ref "21A") (pin "1") (pinfunction "P_1") (pintype "passive"))
      (node (ref "U$1") (pin "P139") (pinfunction "IO_L3N_0_P139") (pintype "bidirectional"))
      (node (ref "U3") (pin "96") (pinfunction "PB9_96") (pintype "bidirectional"))
    )
    (net (code "192") (name "{slash}RFSH") (class "Default")
      (node (ref "23A") (pin "1") (pinfunction "P_1") (pintype "passive"))
      (node (ref "U$1") (pin "P74") (pinfunction "IO_L74N_DOUT_BUSY_1_P74") (pintype "bidirectional"))
    )
    (net (code "193") (name "{slash}WAIT") (class "Default")
      (node (ref "19A") (pin "1") (pinfunction "P_1") (pintype "passive"))
      (node (ref "U3") (pin "23") (pinfunction "PA0_23") (pintype "bidirectional"))
    )
    (net (code "194") (name "{slash}WR") (class "Default")
      (node (ref "17A") (pin "1") (pinfunction "P_1") (pintype "passive"))
      (node (ref "U$1") (pin "P58") (pinfunction "IO_L14P_D11_2_P58") (pintype "bidirectional"))
    )
    (net (code "195") (name "{slash}WR'") (class "Default")
      (node (ref "U$1") (pin "P102") (pinfunction "IO_L32P_1_P102") (pintype "bidirectional"))
      (node (ref "U2") (pin "29") (pinfunction "WE_29") (pintype "input"))
      (node (ref "U3") (pin "26") (pinfunction "PA3_26") (pintype "bidirectional"))
    )
  )
)
